# Main.net
KiCad netlist of a schematic drawn in EAGLE
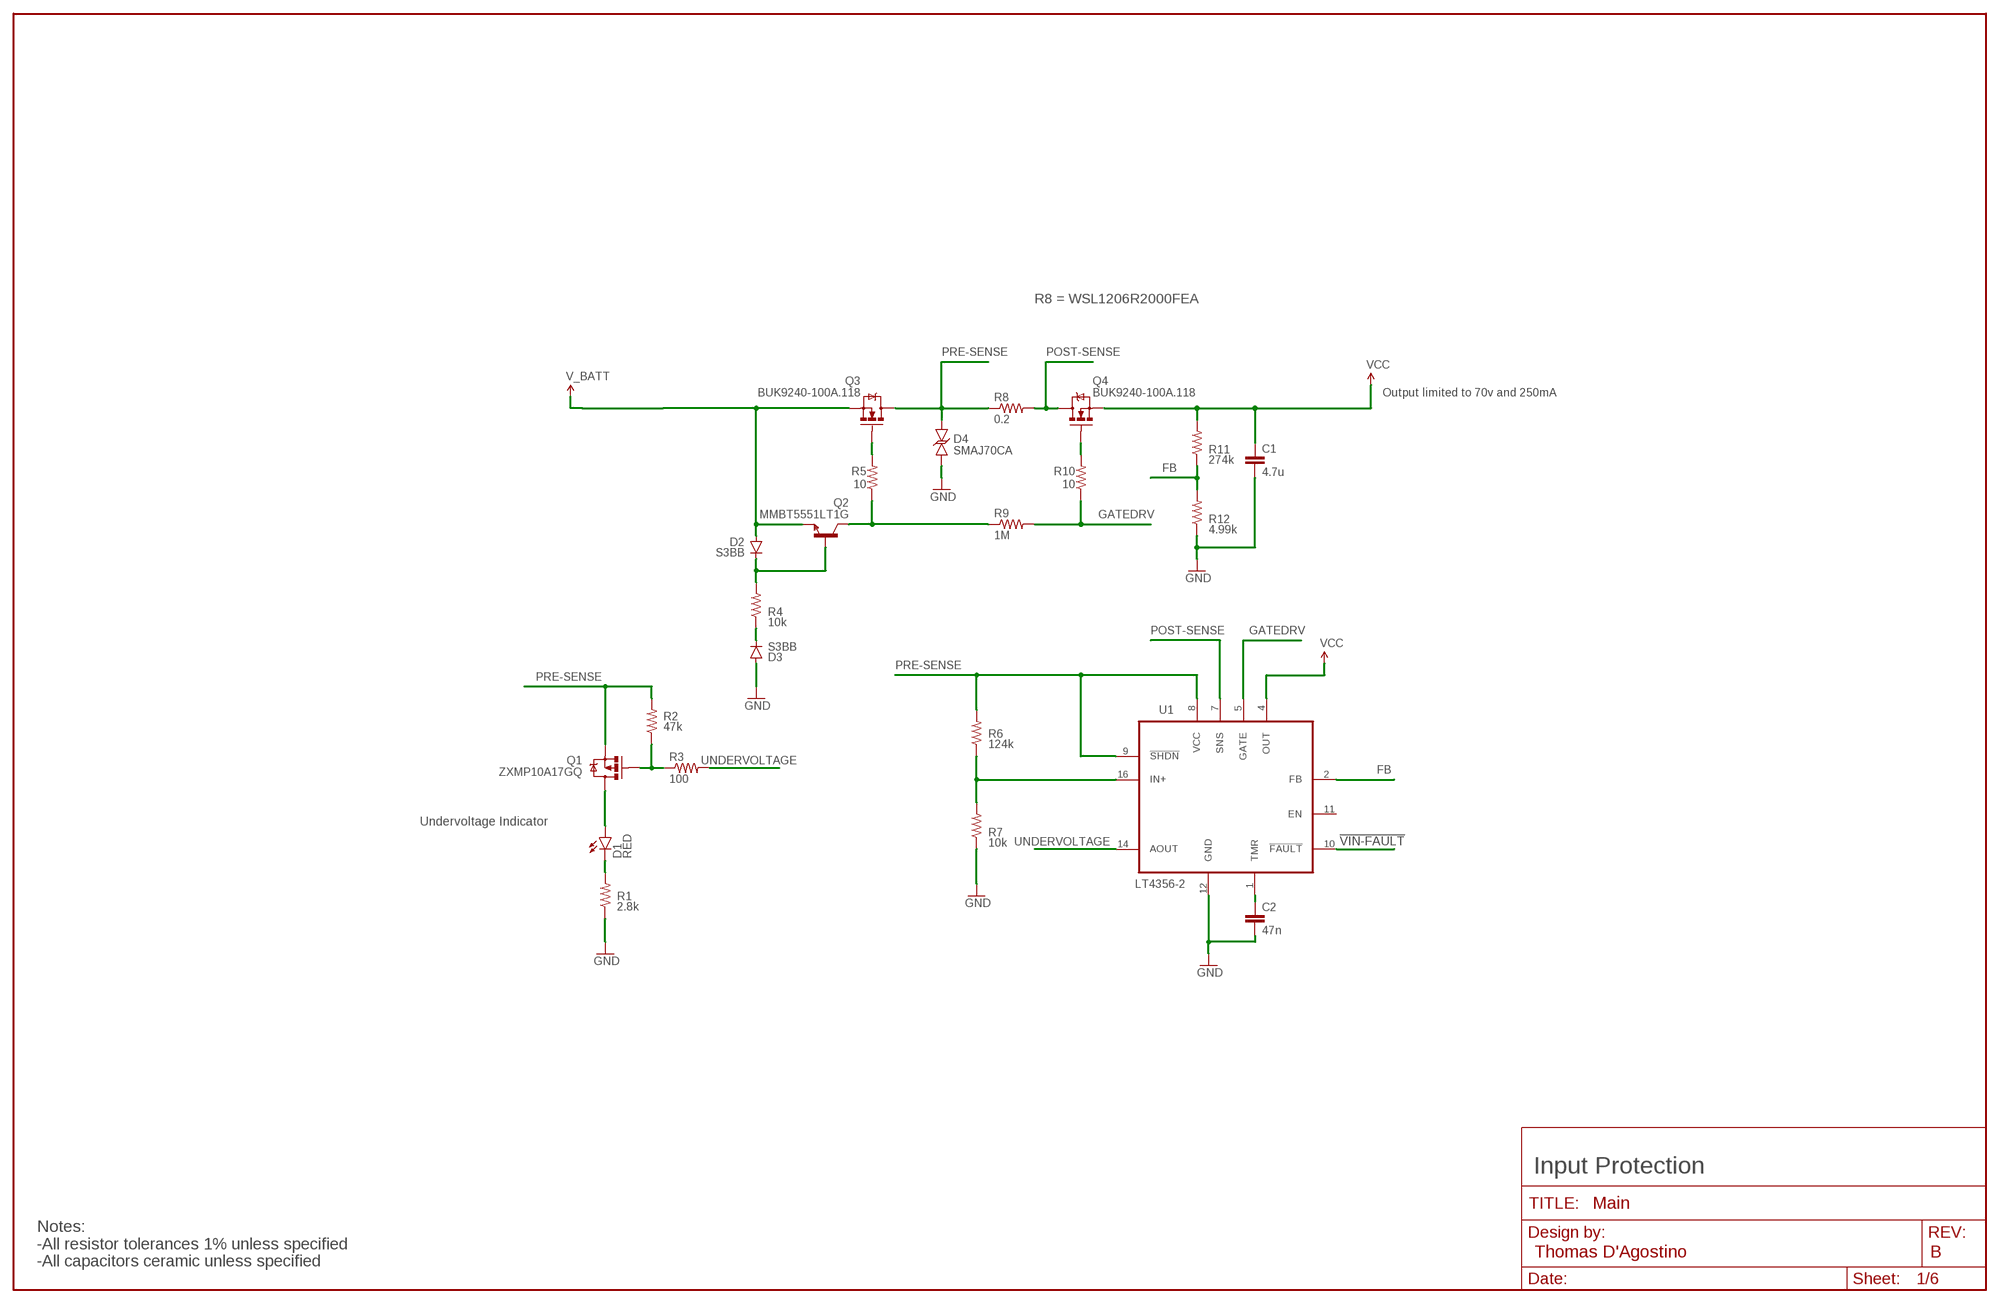
[diagram p0: schematic, sheet 1]
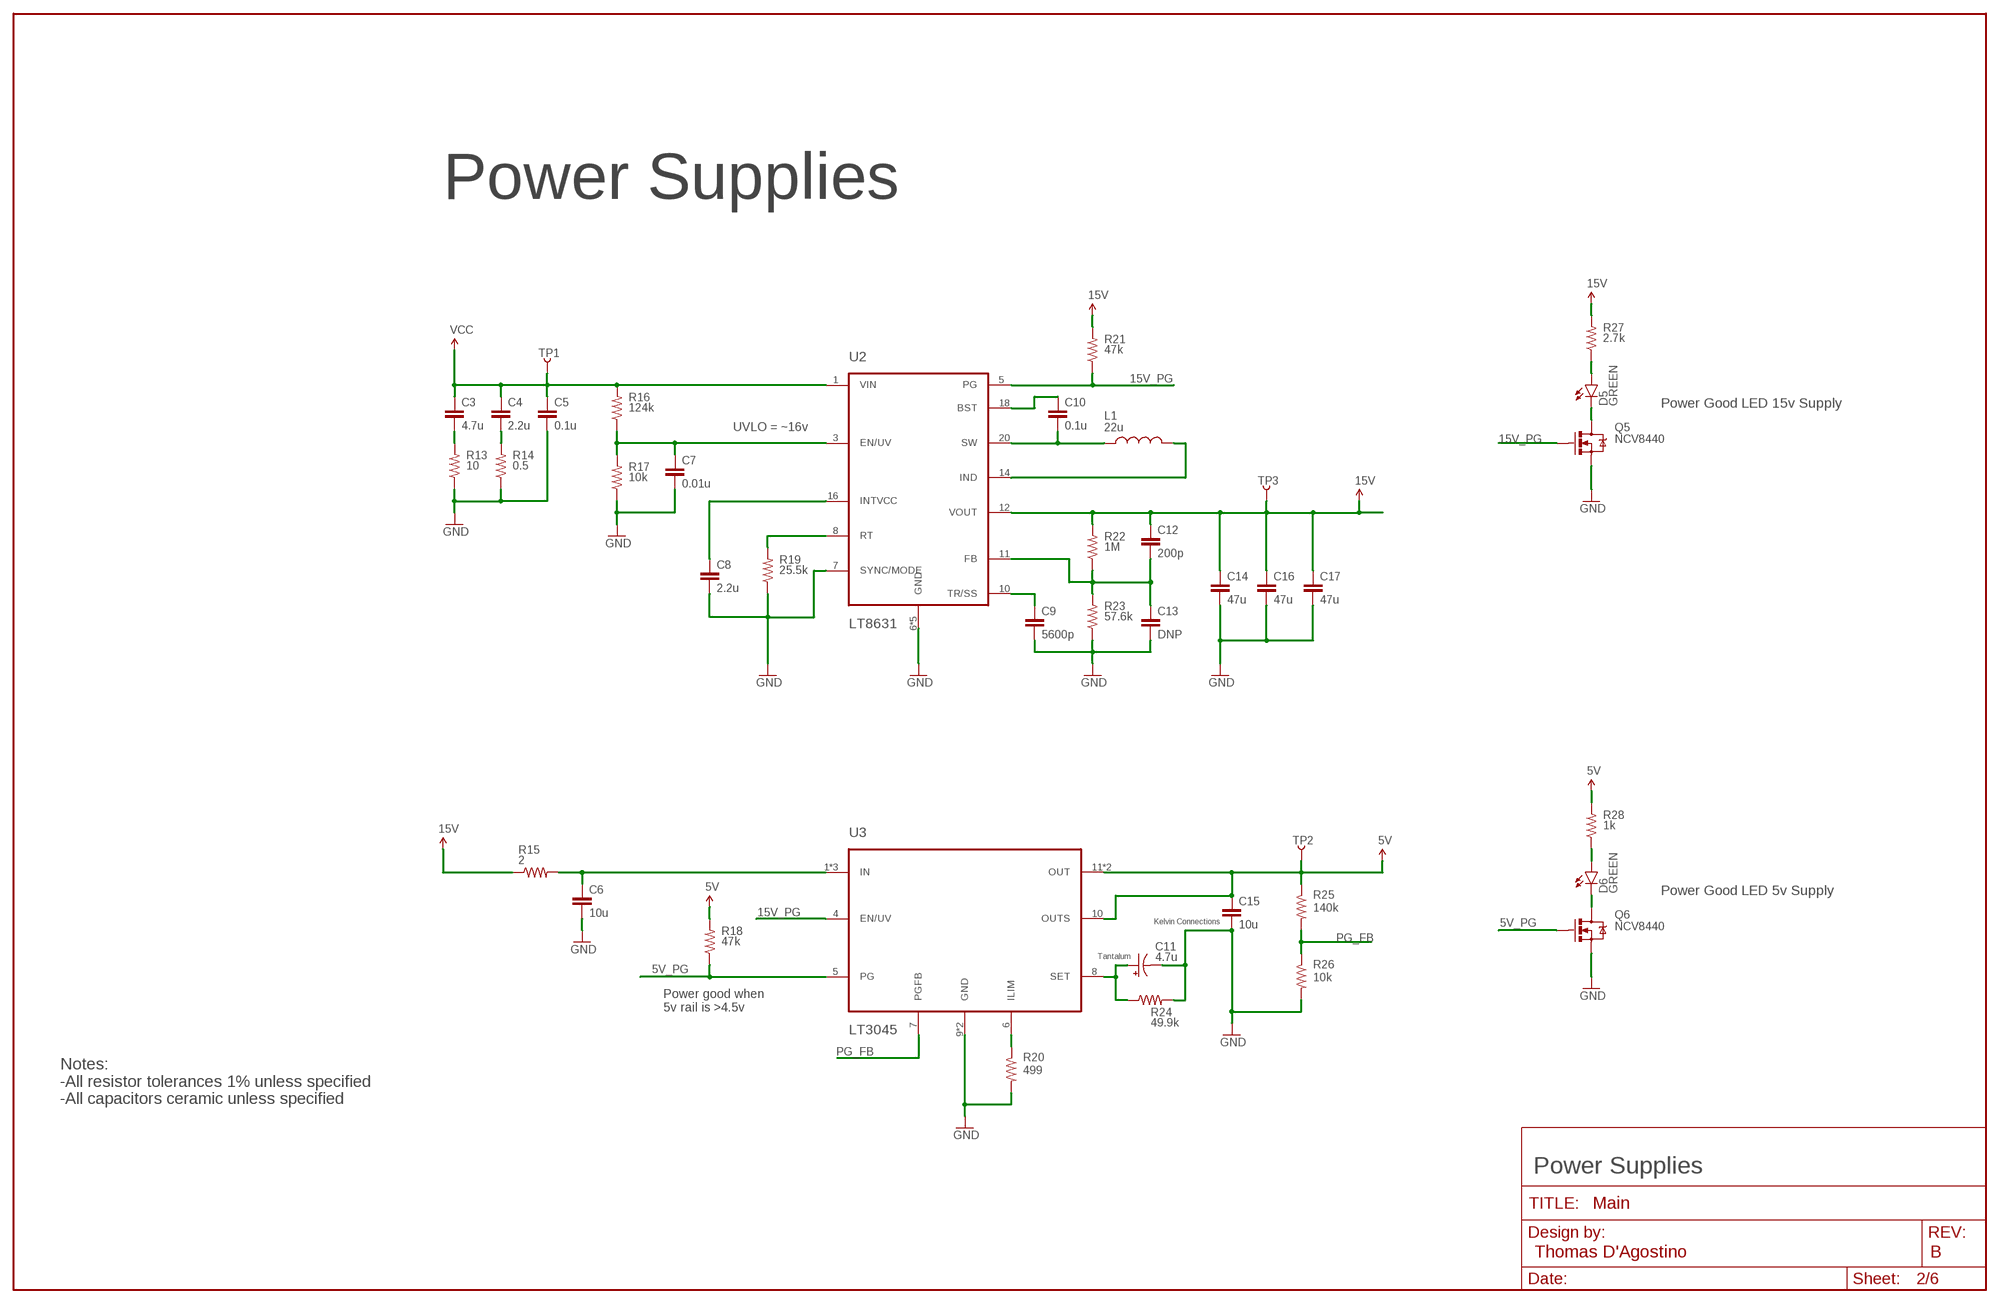
[diagram p1: schematic, sheet 2]
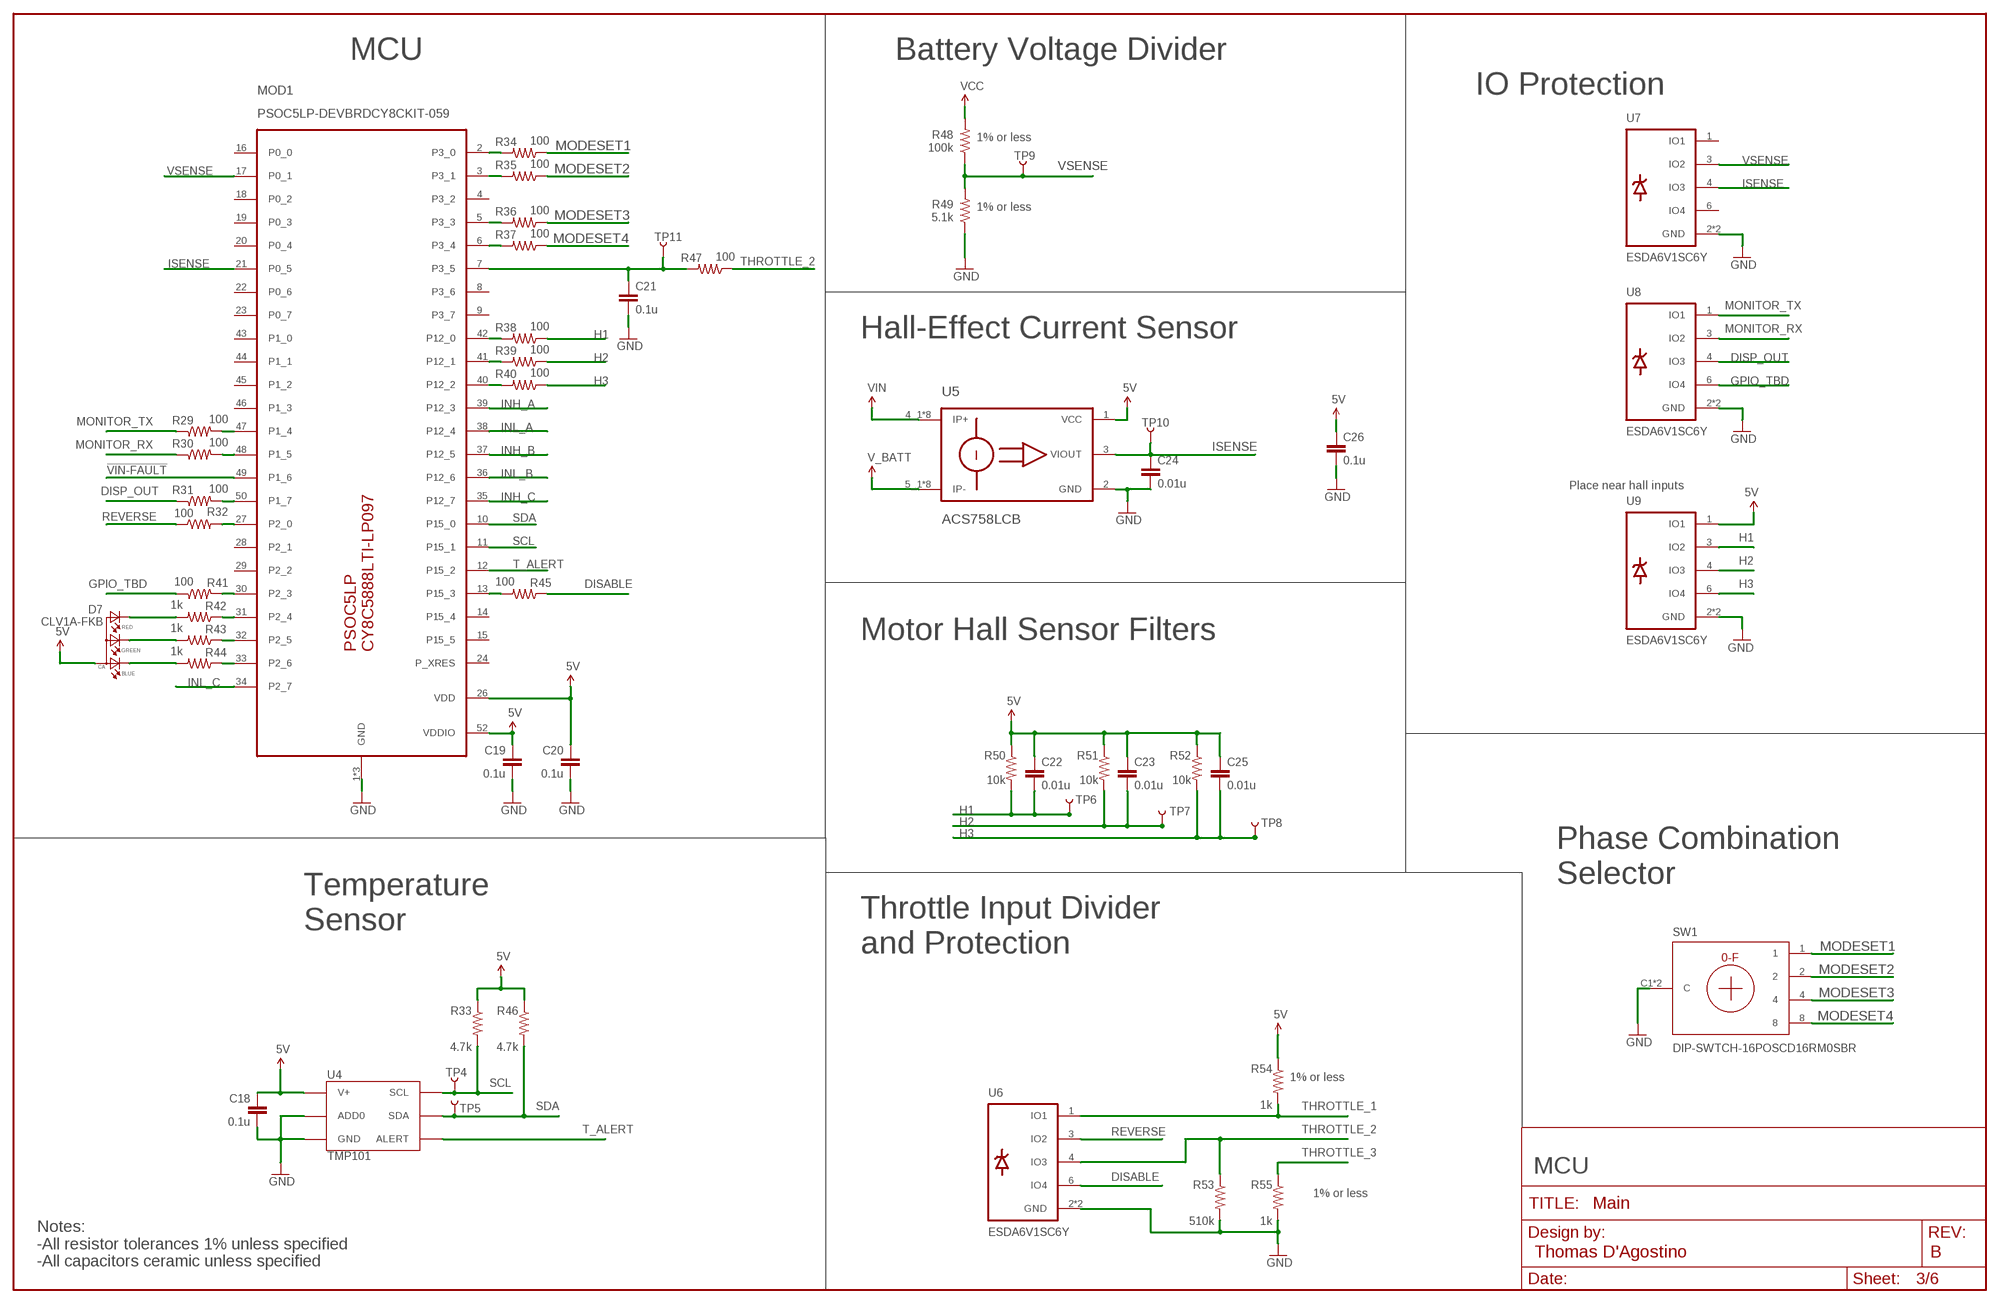
[diagram p2: schematic, sheet 3]
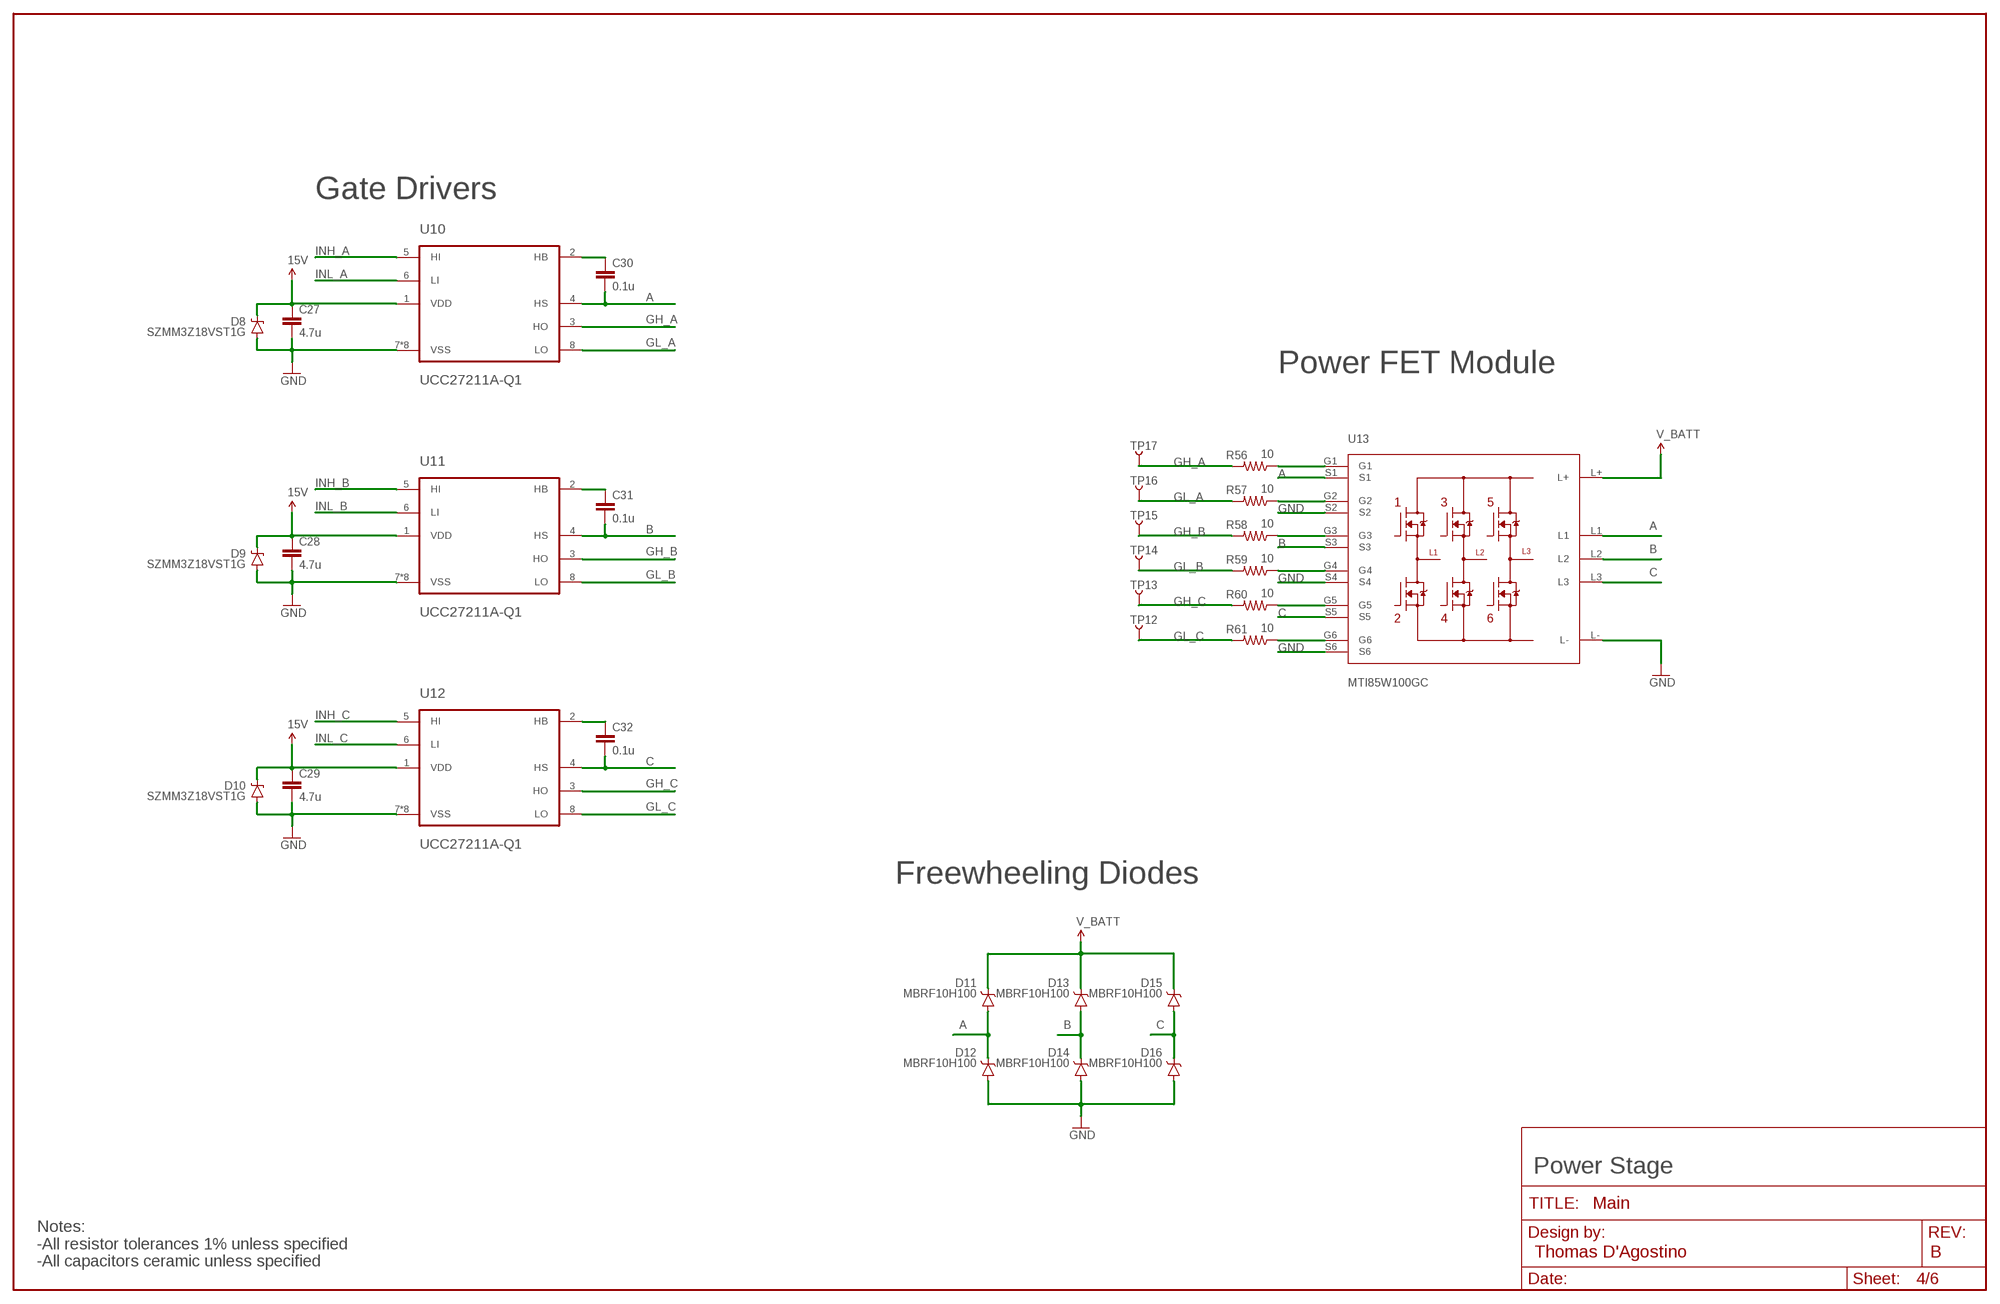
[diagram p3: schematic, sheet 4]
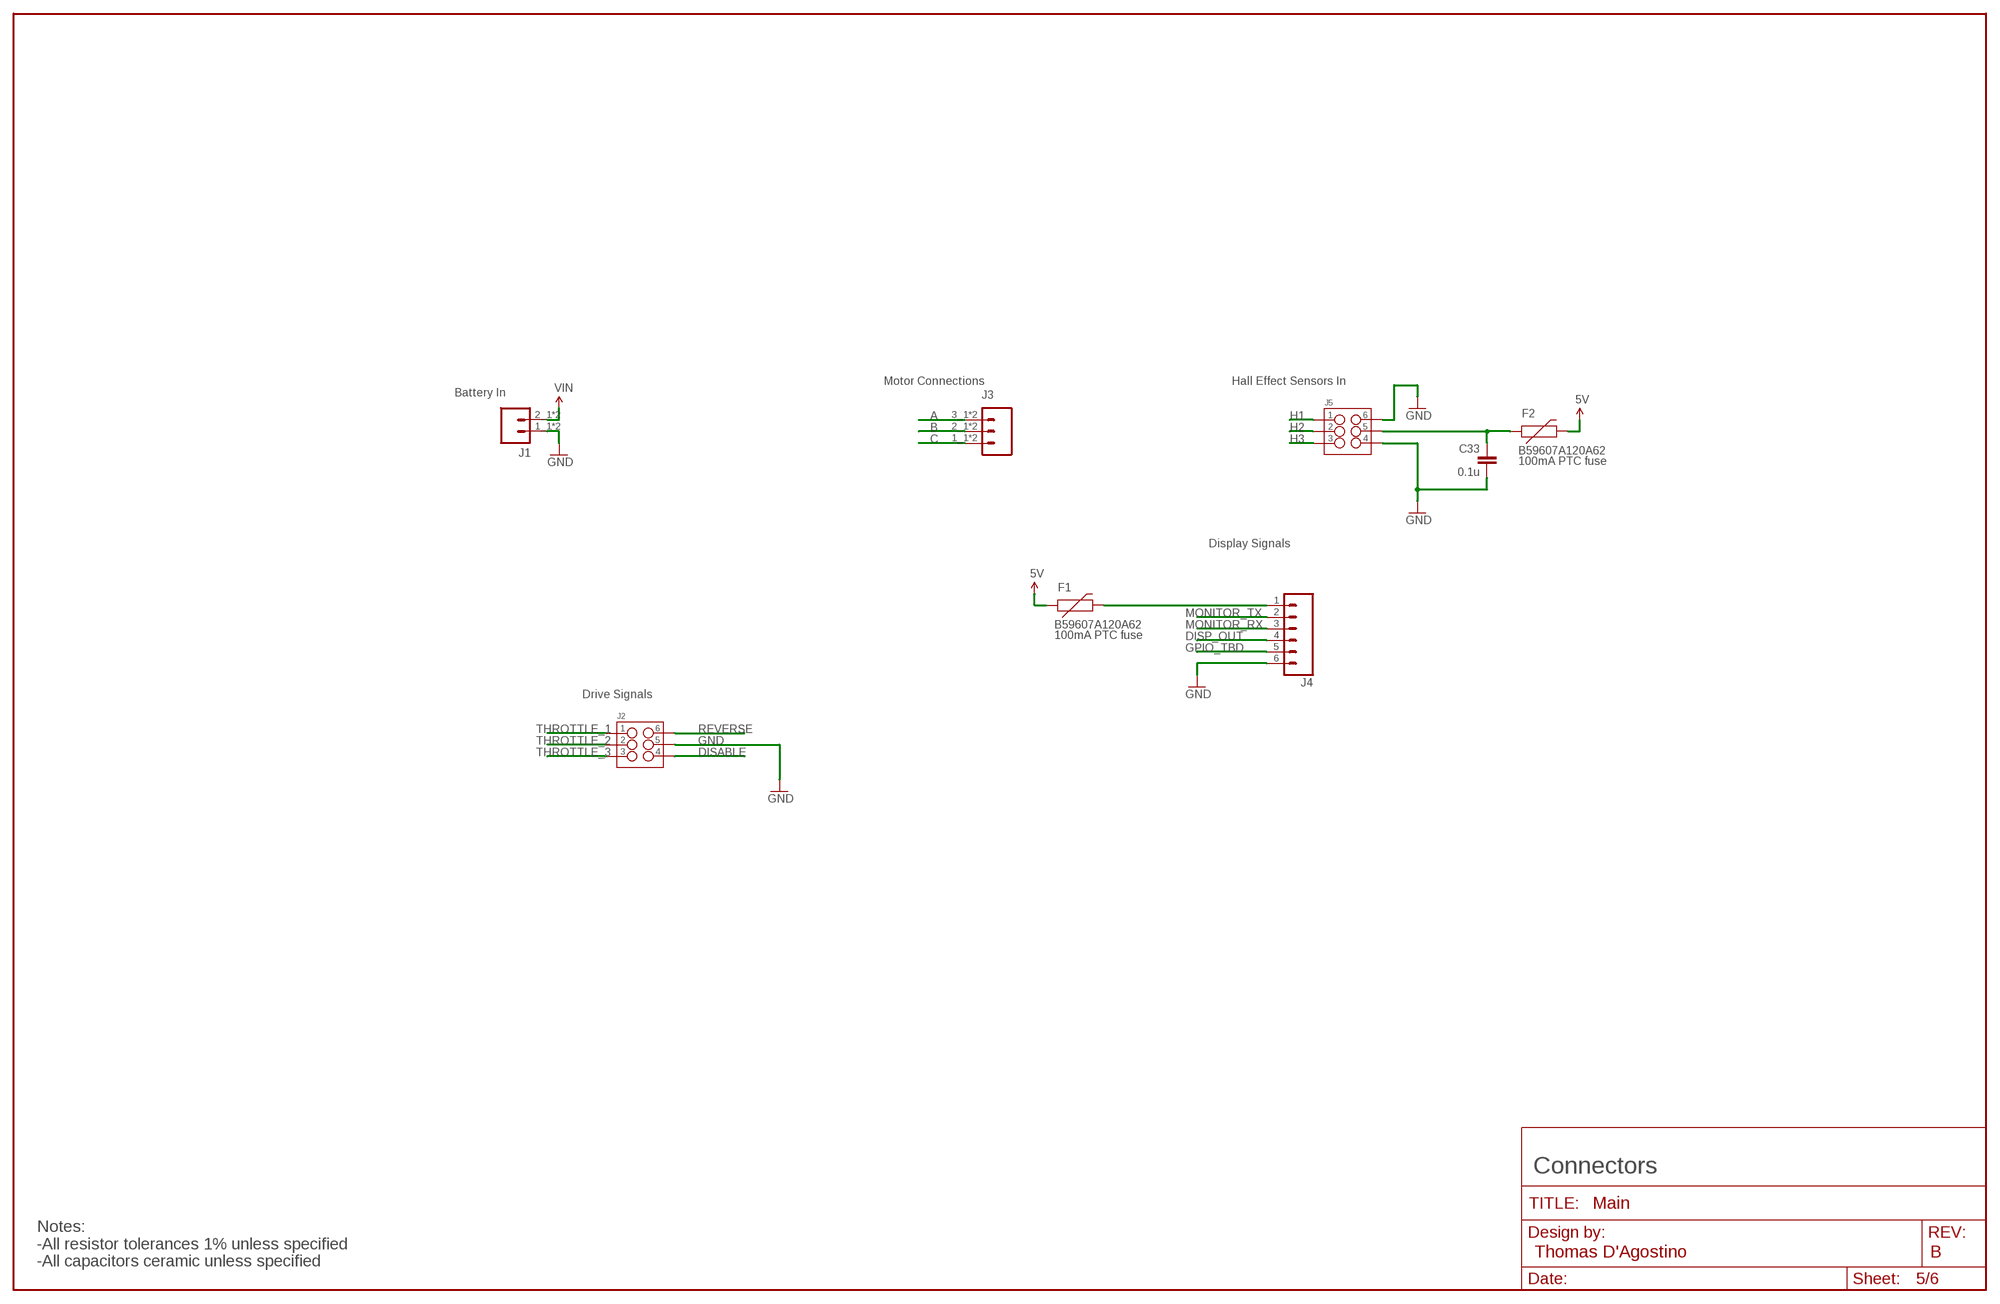
[diagram p4: schematic, sheet 5]
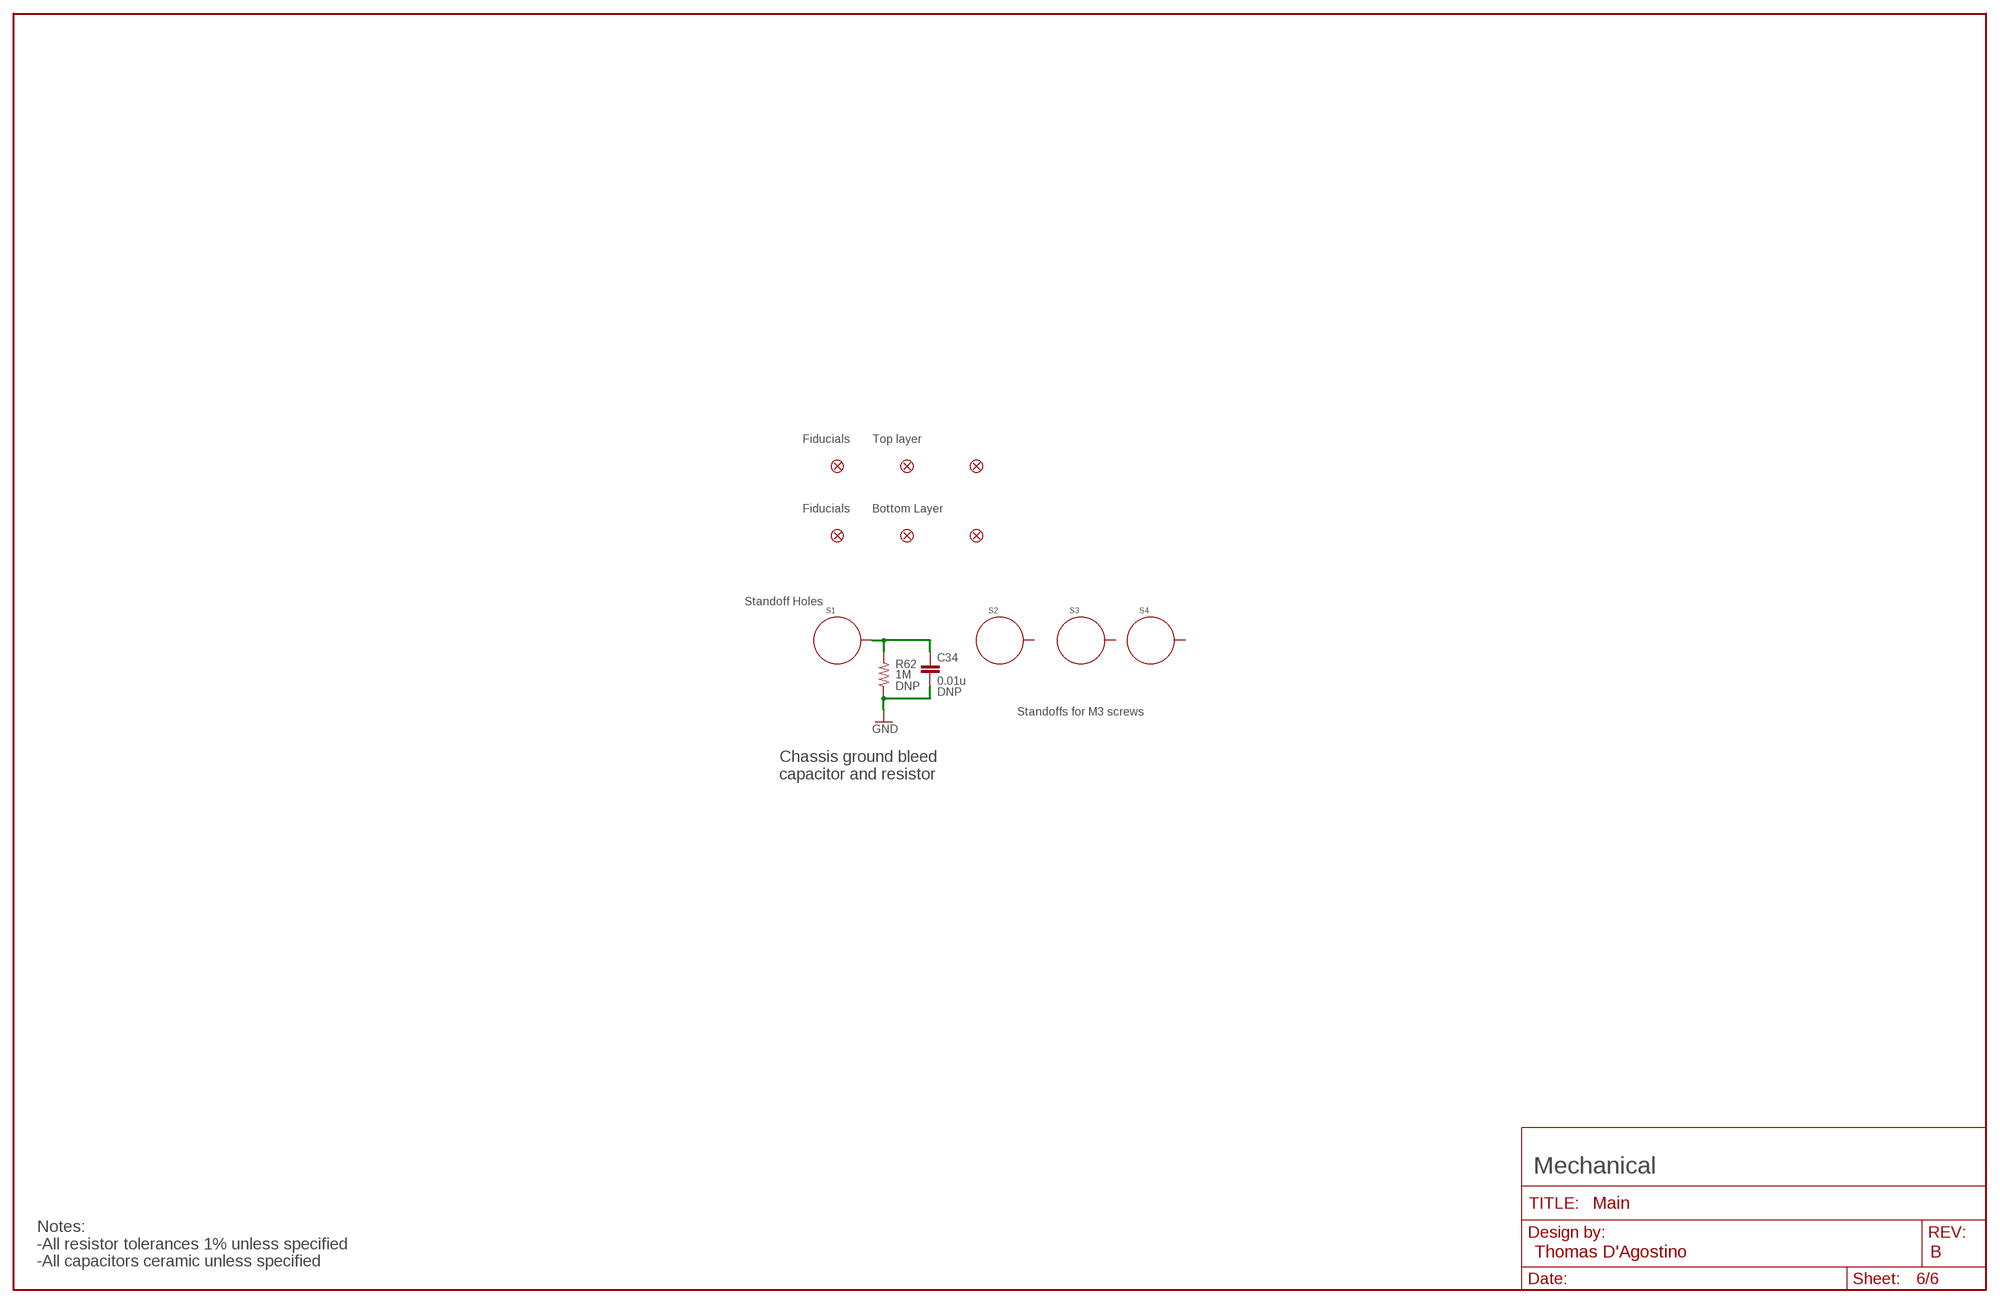
[diagram p5: schematic, sheet 6]

(export (version "E")
  (design (tool "Eeschema 10.0.6"))
  (components
    (comp (ref "C33")
      (value "0.1u")
      (footprint "eagle-import:0805")
      (libsource (lib "eagle-import") (part "CAP0805"))
    )
    (comp (ref "F1")
      (value "B59607A120A62")
      (footprint "eagle-import:1210")
      (libsource (lib "eagle-import") (part "PTC1210"))
    )
    (comp (ref "F2")
      (value "B59607A120A62")
      (footprint "eagle-import:1210")
      (libsource (lib "eagle-import") (part "PTC1210"))
    )
    (comp (ref "FRAME5")
      (value "FRAME-LEDGER")
      (footprint "eagle-import:CREATIVE_COMMONS")
      (libsource (lib "eagle-import") (part "FRAME-LEDGER"))
    )
    (comp (ref "J1")
      (value "M02MINIFIT-SR")
      (footprint "eagle-import:MINIFIT_SR")
      (libsource (lib "eagle-import") (part "M02MINIFIT-SR"))
    )
    (comp (ref "J2")
      (value "M03X2MINIFIT_JR")
      (footprint "eagle-import:2X03_MINIFIT_JR")
      (libsource (lib "eagle-import") (part "M03X2MINIFIT_JR"))
    )
    (comp (ref "J3")
      (value "M03MINIFIT-SR3")
      (footprint "eagle-import:MINIFIT-SRX3")
      (libsource (lib "eagle-import") (part "M03MINIFIT-SR3"))
    )
    (comp (ref "J4")
      (value "M06SILK_FEMALE_PTH")
      (footprint "eagle-import:1X06")
      (libsource (lib "eagle-import") (part "M06SILK_FEMALE_PTH"))
    )
    (comp (ref "J5")
      (value "M03X2MINIFIT_JR")
      (footprint "eagle-import:2X03_MINIFIT_JR")
      (libsource (lib "eagle-import") (part "M03X2MINIFIT_JR"))
    )
    (comp (ref "C18")
      (value "0.1u")
      (footprint "eagle-import:0805")
      (libsource (lib "eagle-import") (part "CAP0805"))
    )
    (comp (ref "C19")
      (value "0.1u")
      (footprint "eagle-import:0805")
      (libsource (lib "eagle-import") (part "CAP0805"))
    )
    (comp (ref "C20")
      (value "0.1u")
      (footprint "eagle-import:0805")
      (libsource (lib "eagle-import") (part "CAP0805"))
    )
    (comp (ref "C21")
      (value "0.1u")
      (footprint "eagle-import:0805")
      (libsource (lib "eagle-import") (part "CAP0805"))
    )
    (comp (ref "C22")
      (value "0.01u")
      (footprint "eagle-import:0805")
      (libsource (lib "eagle-import") (part "CAP0805"))
    )
    (comp (ref "C23")
      (value "0.01u")
      (footprint "eagle-import:0805")
      (libsource (lib "eagle-import") (part "CAP0805"))
    )
    (comp (ref "C24")
      (value "0.01u")
      (footprint "eagle-import:0805")
      (libsource (lib "eagle-import") (part "CAP0805"))
    )
    (comp (ref "C25")
      (value "0.01u")
      (footprint "eagle-import:0805")
      (libsource (lib "eagle-import") (part "CAP0805"))
    )
    (comp (ref "C26")
      (value "0.1u")
      (footprint "eagle-import:0805")
      (libsource (lib "eagle-import") (part "CAP0805"))
    )
    (comp (ref "D7")
      (value "CLV1A-FKB")
      (footprint "eagle-import:P-LCC-4-3")
      (libsource (lib "eagle-import") (part "0.13_RGB_LEDCLV1A-FKB"))
    )
    (comp (ref "FRAME3")
      (value "FRAME-LEDGER")
      (footprint "eagle-import:CREATIVE_COMMONS")
      (libsource (lib "eagle-import") (part "FRAME-LEDGER"))
    )
    (comp (ref "MOD1")
      (value "PSOC5LP-DEVBRDCY8CKIT-059")
      (footprint "eagle-import:CYKIT059")
      (libsource (lib "eagle-import") (part "PSOC5LP-DEVBRDCY8CKIT-059"))
    )
    (comp (ref "R29")
      (value "100")
      (footprint "eagle-import:0805")
      (libsource (lib "eagle-import") (part "SparkFun-Resistors_RESISTOR0805-RES"))
    )
    (comp (ref "R30")
      (value "100")
      (footprint "eagle-import:0805")
      (libsource (lib "eagle-import") (part "SparkFun-Resistors_RESISTOR0805-RES"))
    )
    (comp (ref "R31")
      (value "100")
      (footprint "eagle-import:0805")
      (libsource (lib "eagle-import") (part "SparkFun-Resistors_RESISTOR0805-RES"))
    )
    (comp (ref "R32")
      (value "100")
      (footprint "eagle-import:0805")
      (libsource (lib "eagle-import") (part "SparkFun-Resistors_RESISTOR0805-RES"))
    )
    (comp (ref "R33")
      (value "4.7k")
      (footprint "eagle-import:0805")
      (libsource (lib "eagle-import") (part "SparkFun-Resistors_RESISTOR0805-RES"))
    )
    (comp (ref "R34")
      (value "100")
      (footprint "eagle-import:0805")
      (libsource (lib "eagle-import") (part "SparkFun-Resistors_RESISTOR0805-RES"))
    )
    (comp (ref "R35")
      (value "100")
      (footprint "eagle-import:0805")
      (libsource (lib "eagle-import") (part "SparkFun-Resistors_RESISTOR0805-RES"))
    )
    (comp (ref "R36")
      (value "100")
      (footprint "eagle-import:0805")
      (libsource (lib "eagle-import") (part "SparkFun-Resistors_RESISTOR0805-RES"))
    )
    (comp (ref "R37")
      (value "100")
      (footprint "eagle-import:0805")
      (libsource (lib "eagle-import") (part "SparkFun-Resistors_RESISTOR0805-RES"))
    )
    (comp (ref "R38")
      (value "100")
      (footprint "eagle-import:0805")
      (libsource (lib "eagle-import") (part "SparkFun-Resistors_RESISTOR0805-RES"))
    )
    (comp (ref "R39")
      (value "100")
      (footprint "eagle-import:0805")
      (libsource (lib "eagle-import") (part "SparkFun-Resistors_RESISTOR0805-RES"))
    )
    (comp (ref "R40")
      (value "100")
      (footprint "eagle-import:0805")
      (libsource (lib "eagle-import") (part "SparkFun-Resistors_RESISTOR0805-RES"))
    )
    (comp (ref "R41")
      (value "100")
      (footprint "eagle-import:0805")
      (libsource (lib "eagle-import") (part "SparkFun-Resistors_RESISTOR0805-RES"))
    )
    (comp (ref "R42")
      (value "1k")
      (footprint "eagle-import:0805")
      (libsource (lib "eagle-import") (part "SparkFun-Resistors_RESISTOR0805-RES"))
    )
    (comp (ref "R43")
      (value "1k")
      (footprint "eagle-import:0805")
      (libsource (lib "eagle-import") (part "SparkFun-Resistors_RESISTOR0805-RES"))
    )
    (comp (ref "R44")
      (value "1k")
      (footprint "eagle-import:0805")
      (libsource (lib "eagle-import") (part "SparkFun-Resistors_RESISTOR0805-RES"))
    )
    (comp (ref "R45")
      (value "100")
      (footprint "eagle-import:0805")
      (libsource (lib "eagle-import") (part "SparkFun-Resistors_RESISTOR0805-RES"))
    )
    (comp (ref "R46")
      (value "4.7k")
      (footprint "eagle-import:0805")
      (libsource (lib "eagle-import") (part "SparkFun-Resistors_RESISTOR0805-RES"))
    )
    (comp (ref "R47")
      (value "100")
      (footprint "eagle-import:0805")
      (libsource (lib "eagle-import") (part "SparkFun-Resistors_RESISTOR0805-RES"))
    )
    (comp (ref "R48")
      (value "100k")
      (footprint "eagle-import:1206")
      (libsource (lib "eagle-import") (part "SparkFun-Resistors_RESISTOR1206"))
    )
    (comp (ref "R49")
      (value "5.1k")
      (footprint "eagle-import:1206")
      (libsource (lib "eagle-import") (part "SparkFun-Resistors_RESISTOR1206"))
    )
    (comp (ref "R50")
      (value "10k")
      (footprint "eagle-import:0805")
      (libsource (lib "eagle-import") (part "SparkFun-Resistors_RESISTOR0805-RES"))
    )
    (comp (ref "R51")
      (value "10k")
      (footprint "eagle-import:0805")
      (libsource (lib "eagle-import") (part "SparkFun-Resistors_RESISTOR0805-RES"))
    )
    (comp (ref "R52")
      (value "10k")
      (footprint "eagle-import:0805")
      (libsource (lib "eagle-import") (part "SparkFun-Resistors_RESISTOR0805-RES"))
    )
    (comp (ref "R53")
      (value "510k")
      (footprint "eagle-import:0805")
      (libsource (lib "eagle-import") (part "SparkFun-Resistors_RESISTOR0805-RES"))
    )
    (comp (ref "R54")
      (value "1k")
      (footprint "eagle-import:0805")
      (libsource (lib "eagle-import") (part "SparkFun-Resistors_RESISTOR0805-RES"))
    )
    (comp (ref "R55")
      (value "1k")
      (footprint "eagle-import:0805")
      (libsource (lib "eagle-import") (part "SparkFun-Resistors_RESISTOR0805-RES"))
    )
    (comp (ref "SW1")
      (value "DIP-SWTCH-16POSCD16RM0SBR")
      (footprint "eagle-import:DIP-8MM")
      (libsource (lib "eagle-import") (part "DIP-SWTCH-16POSCD16RM0SBR"))
    )
    (comp (ref "TP4")
      (value "TEST-POINTRCT-0C")
      (footprint "eagle-import:TEST-POINT-MINI")
      (libsource (lib "eagle-import") (part "TEST-POINTRCT-0C"))
    )
    (comp (ref "TP5")
      (value "TEST-POINTRCT-0C")
      (footprint "eagle-import:TEST-POINT-MINI")
      (libsource (lib "eagle-import") (part "TEST-POINTRCT-0C"))
    )
    (comp (ref "TP6")
      (value "TEST-POINTRCT-0C")
      (footprint "eagle-import:TEST-POINT-MINI")
      (libsource (lib "eagle-import") (part "TEST-POINTRCT-0C"))
    )
    (comp (ref "TP7")
      (value "TEST-POINTRCT-0C")
      (footprint "eagle-import:TEST-POINT-MINI")
      (libsource (lib "eagle-import") (part "TEST-POINTRCT-0C"))
    )
    (comp (ref "TP8")
      (value "TEST-POINTRCT-0C")
      (footprint "eagle-import:TEST-POINT-MINI")
      (libsource (lib "eagle-import") (part "TEST-POINTRCT-0C"))
    )
    (comp (ref "TP9")
      (value "TEST-POINTRCT-0C")
      (footprint "eagle-import:TEST-POINT-MINI")
      (libsource (lib "eagle-import") (part "TEST-POINTRCT-0C"))
    )
    (comp (ref "TP10")
      (value "TEST-POINTRCT-0C")
      (footprint "eagle-import:TEST-POINT-MINI")
      (libsource (lib "eagle-import") (part "TEST-POINTRCT-0C"))
    )
    (comp (ref "TP11")
      (value "TEST-POINTRCT-0C")
      (footprint "eagle-import:TEST-POINT-MINI")
      (libsource (lib "eagle-import") (part "TEST-POINTRCT-0C"))
    )
    (comp (ref "U4")
      (value "TMP101")
      (footprint "eagle-import:SOT23-6")
      (libsource (lib "eagle-import") (part "TMP101"))
    )
    (comp (ref "U5")
      (value "ACS758LCB")
      (footprint "eagle-import:CB5PIN")
      (libsource (lib "eagle-import") (part "ACS758LCB"))
    )
    (comp (ref "U6")
      (value "ESDA6V1SC6Y")
      (footprint "eagle-import:SOT23-6")
      (libsource (lib "eagle-import") (part "ESDA6V1SC6Y"))
    )
    (comp (ref "U7")
      (value "ESDA6V1SC6Y")
      (footprint "eagle-import:SOT23-6")
      (libsource (lib "eagle-import") (part "ESDA6V1SC6Y"))
    )
    (comp (ref "U8")
      (value "ESDA6V1SC6Y")
      (footprint "eagle-import:SOT23-6")
      (libsource (lib "eagle-import") (part "ESDA6V1SC6Y"))
    )
    (comp (ref "U9")
      (value "ESDA6V1SC6Y")
      (footprint "eagle-import:SOT23-6")
      (libsource (lib "eagle-import") (part "ESDA6V1SC6Y"))
    )
    (comp (ref "C3")
      (value "4.7u")
      (footprint "eagle-import:1210")
      (libsource (lib "eagle-import") (part "CAP1210"))
    )
    (comp (ref "C4")
      (value "2.2u")
      (footprint "eagle-import:1210")
      (libsource (lib "eagle-import") (part "CAP1210"))
    )
    (comp (ref "C5")
      (value "0.1u")
      (footprint "eagle-import:0805")
      (libsource (lib "eagle-import") (part "CAP0805"))
    )
    (comp (ref "C6")
      (value "10u")
      (footprint "eagle-import:1210")
      (libsource (lib "eagle-import") (part "CAP1210"))
    )
    (comp (ref "C7")
      (value "0.01u")
      (footprint "eagle-import:0805")
      (libsource (lib "eagle-import") (part "CAP0805"))
    )
    (comp (ref "C8")
      (value "2.2u")
      (footprint "eagle-import:0805")
      (libsource (lib "eagle-import") (part "CAP0805"))
    )
    (comp (ref "C9")
      (value "5600p")
      (footprint "eagle-import:0805")
      (libsource (lib "eagle-import") (part "CAP0805"))
    )
    (comp (ref "C10")
      (value "0.1u")
      (footprint "eagle-import:0805")
      (libsource (lib "eagle-import") (part "CAP0805"))
    )
    (comp (ref "C11")
      (value "4.7u")
      (footprint "eagle-import:EIA3216")
      (libsource (lib "eagle-import") (part "CAP_POL1206"))
    )
    (comp (ref "C12")
      (value "200p")
      (footprint "eagle-import:0805")
      (libsource (lib "eagle-import") (part "CAP0805"))
    )
    (comp (ref "C13")
      (value "DNP")
      (footprint "eagle-import:0805")
      (libsource (lib "eagle-import") (part "CAP0805"))
    )
    (comp (ref "C14")
      (value "47u")
      (footprint "eagle-import:1210")
      (libsource (lib "eagle-import") (part "CAP1210"))
    )
    (comp (ref "C15")
      (value "10u")
      (footprint "eagle-import:1210")
      (libsource (lib "eagle-import") (part "CAP1210"))
    )
    (comp (ref "C16")
      (value "47u")
      (footprint "eagle-import:1210")
      (libsource (lib "eagle-import") (part "CAP1210"))
    )
    (comp (ref "C17")
      (value "47u")
      (footprint "eagle-import:1210")
      (libsource (lib "eagle-import") (part "CAP1210"))
    )
    (comp (ref "D5")
      (value "GREEN")
      (footprint "eagle-import:LED-1206")
      (libsource (lib "eagle-import") (part "LED-RED1206"))
    )
    (comp (ref "D6")
      (value "GREEN")
      (footprint "eagle-import:LED-1206")
      (libsource (lib "eagle-import") (part "LED-RED1206"))
    )
    (comp (ref "FRAME2")
      (value "FRAME-LEDGER")
      (footprint "eagle-import:CREATIVE_COMMONS")
      (libsource (lib "eagle-import") (part "FRAME-LEDGER"))
    )
    (comp (ref "L1")
      (value "22u")
      (footprint "eagle-import:IND_SMD_SRP7050TA")
      (libsource (lib "eagle-import") (part "INDUCTORSRP7050TA-220M"))
    )
    (comp (ref "Q5")
      (value "NCV8440")
      (footprint "eagle-import:SOT223")
      (libsource (lib "eagle-import") (part "MOSFET-NCHANNELNCV8440"))
    )
    (comp (ref "Q6")
      (value "NCV8440")
      (footprint "eagle-import:SOT223")
      (libsource (lib "eagle-import") (part "MOSFET-NCHANNELNCV8440"))
    )
    (comp (ref "R13")
      (value "10")
      (footprint "eagle-import:0805")
      (libsource (lib "eagle-import") (part "SparkFun-Resistors_RESISTOR0805-RES"))
    )
    (comp (ref "R14")
      (value "0.5")
      (footprint "eagle-import:0805")
      (libsource (lib "eagle-import") (part "SparkFun-Resistors_RESISTOR0805-RES"))
    )
    (comp (ref "R15")
      (value "2")
      (footprint "eagle-import:1206")
      (libsource (lib "eagle-import") (part "RESISTOR1206"))
    )
    (comp (ref "R16")
      (value "124k")
      (footprint "eagle-import:0805")
      (libsource (lib "eagle-import") (part "SparkFun-Resistors_RESISTOR0805-RES"))
    )
    (comp (ref "R17")
      (value "10k")
      (footprint "eagle-import:0805")
      (libsource (lib "eagle-import") (part "SparkFun-Resistors_RESISTOR0805-RES"))
    )
    (comp (ref "R18")
      (value "47k")
      (footprint "eagle-import:0805")
      (libsource (lib "eagle-import") (part "SparkFun-Resistors_RESISTOR0805-RES"))
    )
    (comp (ref "R19")
      (value "25.5k")
      (footprint "eagle-import:0805")
      (libsource (lib "eagle-import") (part "SparkFun-Resistors_RESISTOR0805-RES"))
    )
    (comp (ref "R20")
      (value "499")
      (footprint "eagle-import:0805")
      (libsource (lib "eagle-import") (part "SparkFun-Resistors_RESISTOR0805-RES"))
    )
    (comp (ref "R21")
      (value "47k")
      (footprint "eagle-import:0805")
      (libsource (lib "eagle-import") (part "SparkFun-Resistors_RESISTOR0805-RES"))
    )
    (comp (ref "R22")
      (value "1M")
      (footprint "eagle-import:0805")
      (libsource (lib "eagle-import") (part "SparkFun-Resistors_RESISTOR0805-RES"))
    )
    (comp (ref "R23")
      (value "57.6k")
      (footprint "eagle-import:0805")
      (libsource (lib "eagle-import") (part "SparkFun-Resistors_RESISTOR0805-RES"))
    )
    (comp (ref "R24")
      (value "49.9k")
      (footprint "eagle-import:0805")
      (libsource (lib "eagle-import") (part "SparkFun-Resistors_RESISTOR0805-RES"))
    )
    (comp (ref "R25")
      (value "140k")
      (footprint "eagle-import:0805")
      (libsource (lib "eagle-import") (part "SparkFun-Resistors_RESISTOR0805-RES"))
    )
    (comp (ref "R26")
      (value "10k")
      (footprint "eagle-import:0805")
      (libsource (lib "eagle-import") (part "SparkFun-Resistors_RESISTOR0805-RES"))
    )
    (comp (ref "R27")
      (value "2.7k")
      (footprint "eagle-import:0805")
      (libsource (lib "eagle-import") (part "SparkFun-Resistors_RESISTOR0805-RES"))
    )
    (comp (ref "R28")
      (value "1k")
      (footprint "eagle-import:0805")
      (libsource (lib "eagle-import") (part "SparkFun-Resistors_RESISTOR0805-RES"))
    )
    (comp (ref "TP1")
      (value "TEST-POINTRCT-0C")
      (footprint "eagle-import:TEST-POINT-MINI")
      (libsource (lib "eagle-import") (part "TEST-POINTRCT-0C"))
    )
    (comp (ref "TP2")
      (value "TEST-POINTRCT-0C")
      (footprint "eagle-import:TEST-POINT-MINI")
      (libsource (lib "eagle-import") (part "TEST-POINTRCT-0C"))
    )
    (comp (ref "TP3")
      (value "TEST-POINTRCT-0C")
      (footprint "eagle-import:TEST-POINT-MINI")
      (libsource (lib "eagle-import") (part "TEST-POINTRCT-0C"))
    )
    (comp (ref "U2")
      (value "LT8631")
      (footprint "eagle-import:TSSOP-20-FE")
      (libsource (lib "eagle-import") (part "LT8631"))
    )
    (comp (ref "U3")
      (value "LT3045")
      (footprint "eagle-import:MSOP-12-EP")
      (libsource (lib "eagle-import") (part "LT3045"))
    )
    (comp (ref "C27")
      (value "4.7u")
      (footprint "eagle-import:1210")
      (libsource (lib "eagle-import") (part "CAP1210"))
    )
    (comp (ref "C28")
      (value "4.7u")
      (footprint "eagle-import:1210")
      (libsource (lib "eagle-import") (part "CAP1210"))
    )
    (comp (ref "C29")
      (value "4.7u")
      (footprint "eagle-import:1210")
      (libsource (lib "eagle-import") (part "CAP1210"))
    )
    (comp (ref "C30")
      (value "0.1u")
      (footprint "eagle-import:0805")
      (libsource (lib "eagle-import") (part "CAP0805"))
    )
    (comp (ref "C31")
      (value "0.1u")
      (footprint "eagle-import:0805")
      (libsource (lib "eagle-import") (part "CAP0805"))
    )
    (comp (ref "C32")
      (value "0.1u")
      (footprint "eagle-import:0805")
      (libsource (lib "eagle-import") (part "CAP0805"))
    )
    (comp (ref "D8")
      (value "SZMM3Z18VST1G")
      (footprint "eagle-import:SOD-323")
      (libsource (lib "eagle-import") (part "DIODE-ZENERSZMM3Z18VST1G"))
    )
    (comp (ref "D9")
      (value "SZMM3Z18VST1G")
      (footprint "eagle-import:SOD-323")
      (libsource (lib "eagle-import") (part "DIODE-ZENERSZMM3Z18VST1G"))
    )
    (comp (ref "D10")
      (value "SZMM3Z18VST1G")
      (footprint "eagle-import:SOD-323")
      (libsource (lib "eagle-import") (part "DIODE-ZENERSZMM3Z18VST1G"))
    )
    (comp (ref "D11")
      (value "MBRF10H100")
      (footprint "eagle-import:TO220V_2")
      (libsource (lib "eagle-import") (part "DIODE-SCHOTTKY-MBRF1090_V"))
    )
    (comp (ref "D12")
      (value "MBRF10H100")
      (footprint "eagle-import:TO220V_2")
      (libsource (lib "eagle-import") (part "DIODE-SCHOTTKY-MBRF1090_V"))
    )
    (comp (ref "D13")
      (value "MBRF10H100")
      (footprint "eagle-import:TO220V_2")
      (libsource (lib "eagle-import") (part "DIODE-SCHOTTKY-MBRF1090_V"))
    )
    (comp (ref "D14")
      (value "MBRF10H100")
      (footprint "eagle-import:TO220V_2")
      (libsource (lib "eagle-import") (part "DIODE-SCHOTTKY-MBRF1090_V"))
    )
    (comp (ref "D15")
      (value "MBRF10H100")
      (footprint "eagle-import:TO220V_2")
      (libsource (lib "eagle-import") (part "DIODE-SCHOTTKY-MBRF1090_V"))
    )
    (comp (ref "D16")
      (value "MBRF10H100")
      (footprint "eagle-import:TO220V_2")
      (libsource (lib "eagle-import") (part "DIODE-SCHOTTKY-MBRF1090_V"))
    )
    (comp (ref "FRAME4")
      (value "FRAME-LEDGER")
      (footprint "eagle-import:CREATIVE_COMMONS")
      (libsource (lib "eagle-import") (part "FRAME-LEDGER"))
    )
    (comp (ref "R56")
      (value "10")
      (footprint "eagle-import:0805")
      (libsource (lib "eagle-import") (part "SparkFun-Resistors_RESISTOR0805-RES"))
    )
    (comp (ref "R57")
      (value "10")
      (footprint "eagle-import:0805")
      (libsource (lib "eagle-import") (part "SparkFun-Resistors_RESISTOR0805-RES"))
    )
    (comp (ref "R58")
      (value "10")
      (footprint "eagle-import:0805")
      (libsource (lib "eagle-import") (part "SparkFun-Resistors_RESISTOR0805-RES"))
    )
    (comp (ref "R59")
      (value "10")
      (footprint "eagle-import:0805")
      (libsource (lib "eagle-import") (part "SparkFun-Resistors_RESISTOR0805-RES"))
    )
    (comp (ref "R60")
      (value "10")
      (footprint "eagle-import:0805")
      (libsource (lib "eagle-import") (part "SparkFun-Resistors_RESISTOR0805-RES"))
    )
    (comp (ref "R61")
      (value "10")
      (footprint "eagle-import:0805")
      (libsource (lib "eagle-import") (part "SparkFun-Resistors_RESISTOR0805-RES"))
    )
    (comp (ref "TP12")
      (value "TEST-POINTRCT-0C")
      (footprint "eagle-import:TEST-POINT-MINI")
      (libsource (lib "eagle-import") (part "TEST-POINTRCT-0C"))
    )
    (comp (ref "TP13")
      (value "TEST-POINTRCT-0C")
      (footprint "eagle-import:TEST-POINT-MINI")
      (libsource (lib "eagle-import") (part "TEST-POINTRCT-0C"))
    )
    (comp (ref "TP14")
      (value "TEST-POINTRCT-0C")
      (footprint "eagle-import:TEST-POINT-MINI")
      (libsource (lib "eagle-import") (part "TEST-POINTRCT-0C"))
    )
    (comp (ref "TP15")
      (value "TEST-POINTRCT-0C")
      (footprint "eagle-import:TEST-POINT-MINI")
      (libsource (lib "eagle-import") (part "TEST-POINTRCT-0C"))
    )
    (comp (ref "TP16")
      (value "TEST-POINTRCT-0C")
      (footprint "eagle-import:TEST-POINT-MINI")
      (libsource (lib "eagle-import") (part "TEST-POINTRCT-0C"))
    )
    (comp (ref "TP17")
      (value "TEST-POINTRCT-0C")
      (footprint "eagle-import:TEST-POINT-MINI")
      (libsource (lib "eagle-import") (part "TEST-POINTRCT-0C"))
    )
    (comp (ref "U10")
      (value "UCC27211A-Q1")
      (footprint "eagle-import:SOIC-8-EP")
      (libsource (lib "eagle-import") (part "UCC27211A-Q1"))
    )
    (comp (ref "U11")
      (value "UCC27211A-Q1")
      (footprint "eagle-import:SOIC-8-EP")
      (libsource (lib "eagle-import") (part "UCC27211A-Q1"))
    )
    (comp (ref "U12")
      (value "UCC27211A-Q1")
      (footprint "eagle-import:SOIC-8-EP")
      (libsource (lib "eagle-import") (part "UCC27211A-Q1"))
    )
    (comp (ref "U13")
      (value "MTI85W100GC")
      (footprint "eagle-import:ISOPLUS-DIL")
      (libsource (lib "eagle-import") (part "MTI85W100GC"))
    )
    (comp (ref "C34")
      (value "0.01u")
      (footprint "eagle-import:0805")
      (libsource (lib "eagle-import") (part "CAP0805"))
    )
    (comp (ref "FD1")
      (value "FIDUCIAL1X2")
      (footprint "eagle-import:FIDUCIAL-1X2")
      (libsource (lib "eagle-import") (part "FIDUCIAL1X2"))
    )
    (comp (ref "FD2")
      (value "FIDUCIAL1X2")
      (footprint "eagle-import:FIDUCIAL-1X2")
      (libsource (lib "eagle-import") (part "FIDUCIAL1X2"))
    )
    (comp (ref "FD3")
      (value "FIDUCIAL1X2")
      (footprint "eagle-import:FIDUCIAL-1X2")
      (libsource (lib "eagle-import") (part "FIDUCIAL1X2"))
    )
    (comp (ref "FD4")
      (value "FIDUCIAL1X2")
      (footprint "eagle-import:FIDUCIAL-1X2")
      (libsource (lib "eagle-import") (part "FIDUCIAL1X2"))
    )
    (comp (ref "FD5")
      (value "FIDUCIAL1X2")
      (footprint "eagle-import:FIDUCIAL-1X2")
      (libsource (lib "eagle-import") (part "FIDUCIAL1X2"))
    )
    (comp (ref "FD6")
      (value "FIDUCIAL1X2")
      (footprint "eagle-import:FIDUCIAL-1X2")
      (libsource (lib "eagle-import") (part "FIDUCIAL1X2"))
    )
    (comp (ref "FRAME6")
      (value "FRAME-LEDGER")
      (footprint "eagle-import:CREATIVE_COMMONS")
      (libsource (lib "eagle-import") (part "FRAME-LEDGER"))
    )
    (comp (ref "R62")
      (value "1M")
      (footprint "eagle-import:1206")
      (libsource (lib "eagle-import") (part "SparkFun-Resistors_RESISTOR1206"))
    )
    (comp (ref "S1")
      (value "STANDOFF_ELECTRICAL")
      (footprint "eagle-import:STANDOFF-ELECTRICAL")
      (libsource (lib "eagle-import") (part "STANDOFF_ELECTRICAL"))
    )
    (comp (ref "S2")
      (value "STANDOFF_ELECTRICAL")
      (footprint "eagle-import:STANDOFF-ELECTRICAL")
      (libsource (lib "eagle-import") (part "STANDOFF_ELECTRICAL"))
    )
    (comp (ref "S3")
      (value "STANDOFF_ELECTRICAL")
      (footprint "eagle-import:STANDOFF-ELECTRICAL")
      (libsource (lib "eagle-import") (part "STANDOFF_ELECTRICAL"))
    )
    (comp (ref "S4")
      (value "STANDOFF_ELECTRICAL")
      (footprint "eagle-import:STANDOFF-ELECTRICAL")
      (libsource (lib "eagle-import") (part "STANDOFF_ELECTRICAL"))
    )
    (comp (ref "C1")
      (value "4.7u")
      (footprint "eagle-import:1210")
      (libsource (lib "eagle-import") (part "SparkFun-Passives_CAP1210"))
    )
    (comp (ref "C2")
      (value "47n")
      (footprint "eagle-import:0805")
      (libsource (lib "eagle-import") (part "CAP0805"))
    )
    (comp (ref "D1")
      (value "RED")
      (footprint "eagle-import:LED-1206")
      (libsource (lib "eagle-import") (part "LED-RED1206"))
    )
    (comp (ref "D2")
      (value "S3BB")
      (footprint "eagle-import:SMB-DIODE")
      (libsource (lib "eagle-import") (part "DIODES3BB"))
    )
    (comp (ref "D3")
      (value "S3BB")
      (footprint "eagle-import:SMB-DIODE")
      (libsource (lib "eagle-import") (part "DIODES3BB"))
    )
    (comp (ref "D4")
      (value "SMAJ70CA")
      (footprint "eagle-import:SMA-DIODE-BI")
      (libsource (lib "eagle-import") (part "SMAJ70CABIDIRECTIONAL"))
    )
    (comp (ref "FRAME1")
      (value "FRAME-LEDGER")
      (footprint "eagle-import:CREATIVE_COMMONS")
      (libsource (lib "eagle-import") (part "FRAME-LEDGER"))
    )
    (comp (ref "Q1")
      (value "ZXMP10A17GQ")
      (footprint "eagle-import:SOT223")
      (libsource (lib "eagle-import") (part "MOSFET-PCHANNELZXMP10A17GQ"))
    )
    (comp (ref "Q2")
      (value "MMBT5551LT1G")
      (footprint "eagle-import:SOT23-3")
      (libsource (lib "eagle-import") (part "TRANSISTOR_NPNMMBT5551LT1G"))
    )
    (comp (ref "Q3")
      (value "BUK9240-100A.118")
      (footprint "eagle-import:DPAK")
      (libsource (lib "eagle-import") (part "MOSFET-NCHANNELBUK9240-100A.118"))
    )
    (comp (ref "Q4")
      (value "BUK9240-100A.118")
      (footprint "eagle-import:DPAK")
      (libsource (lib "eagle-import") (part "MOSFET-NCHANNELBUK9240-100A.118"))
    )
    (comp (ref "R1")
      (value "2.8k")
      (footprint "eagle-import:1206")
      (libsource (lib "eagle-import") (part "SparkFun-Resistors_RESISTOR1206"))
    )
    (comp (ref "R2")
      (value "47k")
      (footprint "eagle-import:0805")
      (libsource (lib "eagle-import") (part "SparkFun-Resistors_RESISTOR0805-RES"))
    )
    (comp (ref "R3")
      (value "100")
      (footprint "eagle-import:0805")
      (libsource (lib "eagle-import") (part "SparkFun-Resistors_RESISTOR0805-RES"))
    )
    (comp (ref "R4")
      (value "10k")
      (footprint "eagle-import:0805")
      (libsource (lib "eagle-import") (part "SparkFun-Resistors_RESISTOR0805-RES"))
    )
    (comp (ref "R5")
      (value "10")
      (footprint "eagle-import:0805")
      (libsource (lib "eagle-import") (part "SparkFun-Resistors_RESISTOR0805-RES"))
    )
    (comp (ref "R6")
      (value "124k")
      (footprint "eagle-import:0805")
      (libsource (lib "eagle-import") (part "SparkFun-Resistors_RESISTOR0805-RES"))
    )
    (comp (ref "R7")
      (value "10k")
      (footprint "eagle-import:0805")
      (libsource (lib "eagle-import") (part "SparkFun-Resistors_RESISTOR0805-RES"))
    )
    (comp (ref "R8")
      (value "0.2")
      (footprint "eagle-import:1206")
      (libsource (lib "eagle-import") (part "SparkFun-Resistors_RESISTOR1206"))
    )
    (comp (ref "R9")
      (value "1M")
      (footprint "eagle-import:0805")
      (libsource (lib "eagle-import") (part "SparkFun-Resistors_RESISTOR0805-RES"))
    )
    (comp (ref "R10")
      (value "10")
      (footprint "eagle-import:0805")
      (libsource (lib "eagle-import") (part "SparkFun-Resistors_RESISTOR0805-RES"))
    )
    (comp (ref "R11")
      (value "274k")
      (footprint "eagle-import:0805")
      (libsource (lib "eagle-import") (part "SparkFun-Resistors_RESISTOR0805-RES"))
    )
    (comp (ref "R12")
      (value "4.99k")
      (footprint "eagle-import:0805")
      (libsource (lib "eagle-import") (part "SparkFun-Resistors_RESISTOR0805-RES"))
    )
    (comp (ref "U1")
      (value "LT4356-2")
      (footprint "eagle-import:SOIC-16")
      (libsource (lib "eagle-import") (part "LT4356-2"))
    )
  )
  (nets
    (net (code "1") (name "5V") (class "Default")
      (node (ref "C15") (pin "1") (pinfunction "1_1") (pintype "passive"))
      (node (ref "C18") (pin "1") (pinfunction "1_1") (pintype "passive"))
      (node (ref "C19") (pin "1") (pinfunction "1_1") (pintype "passive"))
      (node (ref "C20") (pin "1") (pinfunction "1_1") (pintype "passive"))
      (node (ref "C22") (pin "1") (pinfunction "1_1") (pintype "passive"))
      (node (ref "C23") (pin "1") (pinfunction "1_1") (pintype "passive"))
      (node (ref "C25") (pin "1") (pinfunction "1_1") (pintype "passive"))
      (node (ref "C26") (pin "1") (pinfunction "1_1") (pintype "passive"))
      (node (ref "D7") (pin "2") (pinfunction "ANODE_2") (pintype "passive"))
      (node (ref "F1") (pin "1") (pinfunction "1_1") (pintype "bidirectional"))
      (node (ref "F2") (pin "2") (pinfunction "2_2") (pintype "bidirectional"))
      (node (ref "MOD1") (pin "26") (pinfunction "VDD_26") (pintype "power_in"))
      (node (ref "MOD1") (pin "52") (pinfunction "VDDIO_52") (pintype "power_in"))
      (node (ref "R18") (pin "2") (pinfunction "2_2") (pintype "passive"))
      (node (ref "R25") (pin "1") (pinfunction "1_1") (pintype "passive"))
      (node (ref "R28") (pin "2") (pinfunction "2_2") (pintype "passive"))
      (node (ref "R33") (pin "1") (pinfunction "1_1") (pintype "passive"))
      (node (ref "R46") (pin "1") (pinfunction "1_1") (pintype "passive"))
      (node (ref "R50") (pin "1") (pinfunction "1_1") (pintype "passive"))
      (node (ref "R51") (pin "1") (pinfunction "1_1") (pintype "passive"))
      (node (ref "R52") (pin "1") (pinfunction "1_1") (pintype "passive"))
      (node (ref "R54") (pin "1") (pinfunction "1_1") (pintype "passive"))
      (node (ref "TP2") (pin "P$1") (pinfunction "1_P$1") (pintype "bidirectional"))
      (node (ref "U3") (pin "10") (pinfunction "OUTS_10") (pintype "input"))
      (node (ref "U3") (pin "11") (pinfunction "OUT_11") (pintype "power_in"))
      (node (ref "U3") (pin "12") (pinfunction "OUT_12") (pintype "power_in"))
      (node (ref "U4") (pin "4") (pinfunction "V+_4") (pintype "power_in"))
      (node (ref "U5") (pin "1") (pinfunction "VCC_1") (pintype "power_in"))
      (node (ref "U9") (pin "1") (pinfunction "IO1_1") (pintype "passive"))
    )
    (net (code "2") (name "5V_PG") (class "Default")
      (node (ref "Q6") (pin "1") (pinfunction "G_1") (pintype "passive"))
      (node (ref "R18") (pin "1") (pinfunction "1_1") (pintype "passive"))
      (node (ref "U3") (pin "5") (pinfunction "PG_5") (pintype "open_collector"))
    )
    (net (code "3") (name "15V") (class "Default")
      (node (ref "C12") (pin "1") (pinfunction "1_1") (pintype "passive"))
      (node (ref "C14") (pin "1") (pinfunction "1_1") (pintype "passive"))
      (node (ref "C16") (pin "1") (pinfunction "1_1") (pintype "passive"))
      (node (ref "C17") (pin "1") (pinfunction "1_1") (pintype "passive"))
      (node (ref "C27") (pin "1") (pinfunction "1_1") (pintype "passive"))
      (node (ref "C28") (pin "1") (pinfunction "1_1") (pintype "passive"))
      (node (ref "C29") (pin "1") (pinfunction "1_1") (pintype "passive"))
      (node (ref "D10") (pin "C") (pinfunction "C_C") (pintype "passive"))
      (node (ref "D8") (pin "C") (pinfunction "C_C") (pintype "passive"))
      (node (ref "D9") (pin "C") (pinfunction "C_C") (pintype "passive"))
      (node (ref "R15") (pin "1") (pinfunction "1_1") (pintype "passive"))
      (node (ref "R21") (pin "2") (pinfunction "2_2") (pintype "passive"))
      (node (ref "R22") (pin "2") (pinfunction "2_2") (pintype "passive"))
      (node (ref "R27") (pin "2") (pinfunction "2_2") (pintype "passive"))
      (node (ref "TP3") (pin "P$1") (pinfunction "1_P$1") (pintype "bidirectional"))
      (node (ref "U10") (pin "1") (pinfunction "VDD_1") (pintype "power_in"))
      (node (ref "U11") (pin "1") (pinfunction "VDD_1") (pintype "power_in"))
      (node (ref "U12") (pin "1") (pinfunction "VDD_1") (pintype "power_in"))
      (node (ref "U2") (pin "12") (pinfunction "VOUT_12") (pintype "passive"))
    )
    (net (code "4") (name "15V_PG") (class "Default")
      (node (ref "Q5") (pin "1") (pinfunction "G_1") (pintype "passive"))
      (node (ref "R21") (pin "1") (pinfunction "1_1") (pintype "passive"))
      (node (ref "U2") (pin "5") (pinfunction "PG_5") (pintype "open_collector"))
      (node (ref "U3") (pin "4") (pinfunction "EN/UV_4") (pintype "input"))
    )
    (net (code "5") (name "A") (class "Default")
      (node (ref "C30") (pin "2") (pinfunction "2_2") (pintype "passive"))
      (node (ref "D11") (pin "2") (pinfunction "A_2") (pintype "passive"))
      (node (ref "D12") (pin "1") (pinfunction "C_1") (pintype "passive"))
      (node (ref "J3") (pin "3_1") (pinfunction "3_3_1") (pintype "passive"))
      (node (ref "J3") (pin "3_2") (pinfunction "3_3_2") (pintype "passive"))
      (node (ref "U10") (pin "4") (pinfunction "HS_4") (pintype "bidirectional"))
      (node (ref "U13") (pin "L1") (pinfunction "L1_L1") (pintype "output"))
      (node (ref "U13") (pin "S1") (pinfunction "S1_S1") (pintype "input"))
    )
    (net (code "6") (name "B") (class "Default")
      (node (ref "C31") (pin "2") (pinfunction "2_2") (pintype "passive"))
      (node (ref "D13") (pin "2") (pinfunction "A_2") (pintype "passive"))
      (node (ref "D14") (pin "1") (pinfunction "C_1") (pintype "passive"))
      (node (ref "J3") (pin "2_1") (pinfunction "2_2_1") (pintype "passive"))
      (node (ref "J3") (pin "2_2") (pinfunction "2_2_2") (pintype "passive"))
      (node (ref "U11") (pin "4") (pinfunction "HS_4") (pintype "bidirectional"))
      (node (ref "U13") (pin "L2") (pinfunction "L2_L2") (pintype "output"))
      (node (ref "U13") (pin "S3") (pinfunction "S3_S3") (pintype "input"))
    )
    (net (code "7") (name "C") (class "Default")
      (node (ref "C32") (pin "2") (pinfunction "2_2") (pintype "passive"))
      (node (ref "D15") (pin "2") (pinfunction "A_2") (pintype "passive"))
      (node (ref "D16") (pin "1") (pinfunction "C_1") (pintype "passive"))
      (node (ref "J3") (pin "1_1") (pinfunction "1_1_1") (pintype "passive"))
      (node (ref "J3") (pin "1_2") (pinfunction "1_1_2") (pintype "passive"))
      (node (ref "U12") (pin "4") (pinfunction "HS_4") (pintype "bidirectional"))
      (node (ref "U13") (pin "L3") (pinfunction "L3_L3") (pintype "output"))
      (node (ref "U13") (pin "S5") (pinfunction "S5_S5") (pintype "input"))
    )
    (net (code "8") (name "DISABLE") (class "Default")
      (node (ref "J2") (pin "4") (pinfunction "4_4") (pintype "bidirectional"))
      (node (ref "R45") (pin "1") (pinfunction "1_1") (pintype "passive"))
      (node (ref "U6") (pin "6") (pinfunction "IO4_6") (pintype "passive"))
    )
    (net (code "9") (name "DISP_OUT") (class "Default")
      (node (ref "J4") (pin "4") (pinfunction "4_4") (pintype "passive"))
      (node (ref "R31") (pin "1") (pinfunction "1_1") (pintype "passive"))
      (node (ref "U8") (pin "6") (pinfunction "IO4_6") (pintype "passive"))
    )
    (net (code "10") (name "FB") (class "Default")
      (node (ref "R11") (pin "1") (pinfunction "1_1") (pintype "passive"))
      (node (ref "R12") (pin "2") (pinfunction "2_2") (pintype "passive"))
      (node (ref "U1") (pin "2") (pinfunction "FB_2") (pintype "input"))
    )
    (net (code "11") (name "GATEDRV") (class "Default")
      (node (ref "R10") (pin "1") (pinfunction "1_1") (pintype "passive"))
      (node (ref "R9") (pin "2") (pinfunction "2_2") (pintype "passive"))
      (node (ref "U1") (pin "5") (pinfunction "GATE_5") (pintype "output"))
    )
    (net (code "12") (name "GH_A") (class "Default")
      (node (ref "R56") (pin "2") (pinfunction "2_2") (pintype "passive"))
      (node (ref "TP17") (pin "P$1") (pinfunction "1_P$1") (pintype "bidirectional"))
      (node (ref "U10") (pin "3") (pinfunction "HO_3") (pintype "output"))
    )
    (net (code "13") (name "GH_B") (class "Default")
      (node (ref "R58") (pin "2") (pinfunction "2_2") (pintype "passive"))
      (node (ref "TP15") (pin "P$1") (pinfunction "1_P$1") (pintype "bidirectional"))
      (node (ref "U11") (pin "3") (pinfunction "HO_3") (pintype "output"))
    )
    (net (code "14") (name "GH_C") (class "Default")
      (node (ref "R60") (pin "2") (pinfunction "2_2") (pintype "passive"))
      (node (ref "TP13") (pin "P$1") (pinfunction "1_P$1") (pintype "bidirectional"))
      (node (ref "U12") (pin "3") (pinfunction "HO_3") (pintype "output"))
    )
    (net (code "15") (name "GL_A") (class "Default")
      (node (ref "R57") (pin "2") (pinfunction "2_2") (pintype "passive"))
      (node (ref "TP16") (pin "P$1") (pinfunction "1_P$1") (pintype "bidirectional"))
      (node (ref "U10") (pin "8") (pinfunction "LO_8") (pintype "output"))
    )
    (net (code "16") (name "GL_B") (class "Default")
      (node (ref "R59") (pin "2") (pinfunction "2_2") (pintype "passive"))
      (node (ref "TP14") (pin "P$1") (pinfunction "1_P$1") (pintype "bidirectional"))
      (node (ref "U11") (pin "8") (pinfunction "LO_8") (pintype "output"))
    )
    (net (code "17") (name "GL_C") (class "Default")
      (node (ref "R61") (pin "2") (pinfunction "2_2") (pintype "passive"))
      (node (ref "TP12") (pin "P$1") (pinfunction "1_P$1") (pintype "bidirectional"))
      (node (ref "U12") (pin "8") (pinfunction "LO_8") (pintype "output"))
    )
    (net (code "18") (name "GND") (class "Default")
      (node (ref "C1") (pin "2") (pinfunction "2_2") (pintype "passive"))
      (node (ref "C11") (pin "C") (pinfunction "-_C") (pintype "passive"))
      (node (ref "C13") (pin "2") (pinfunction "2_2") (pintype "passive"))
      (node (ref "C14") (pin "2") (pinfunction "2_2") (pintype "passive"))
      (node (ref "C15") (pin "2") (pinfunction "2_2") (pintype "passive"))
      (node (ref "C16") (pin "2") (pinfunction "2_2") (pintype "passive"))
      (node (ref "C17") (pin "2") (pinfunction "2_2") (pintype "passive"))
      (node (ref "C18") (pin "2") (pinfunction "2_2") (pintype "passive"))
      (node (ref "C19") (pin "2") (pinfunction "2_2") (pintype "passive"))
      (node (ref "C2") (pin "2") (pinfunction "2_2") (pintype "passive"))
      (node (ref "C20") (pin "2") (pinfunction "2_2") (pintype "passive"))
      (node (ref "C21") (pin "2") (pinfunction "2_2") (pintype "passive"))
      (node (ref "C24") (pin "2") (pinfunction "2_2") (pintype "passive"))
      (node (ref "C26") (pin "2") (pinfunction "2_2") (pintype "passive"))
      (node (ref "C27") (pin "2") (pinfunction "2_2") (pintype "passive"))
      (node (ref "C28") (pin "2") (pinfunction "2_2") (pintype "passive"))
      (node (ref "C29") (pin "2") (pinfunction "2_2") (pintype "passive"))
      (node (ref "C33") (pin "2") (pinfunction "2_2") (pintype "passive"))
      (node (ref "C34") (pin "2") (pinfunction "2_2") (pintype "passive"))
      (node (ref "C5") (pin "2") (pinfunction "2_2") (pintype "passive"))
      (node (ref "C6") (pin "2") (pinfunction "2_2") (pintype "passive"))
      (node (ref "C7") (pin "2") (pinfunction "2_2") (pintype "passive"))
      (node (ref "C8") (pin "2") (pinfunction "2_2") (pintype "passive"))
      (node (ref "C9") (pin "2") (pinfunction "2_2") (pintype "passive"))
      (node (ref "D10") (pin "A") (pinfunction "A_A") (pintype "passive"))
      (node (ref "D12") (pin "2") (pinfunction "A_2") (pintype "passive"))
      (node (ref "D14") (pin "2") (pinfunction "A_2") (pintype "passive"))
      (node (ref "D16") (pin "2") (pinfunction "A_2") (pintype "passive"))
      (node (ref "D3") (pin "A") (pinfunction "A_A") (pintype "passive"))
      (node (ref "D4") (pin "A") (pinfunction "A_A") (pintype "passive"))
      (node (ref "D8") (pin "A") (pinfunction "A_A") (pintype "passive"))
      (node (ref "D9") (pin "A") (pinfunction "A_A") (pintype "passive"))
      (node (ref "J1") (pin "1_1") (pinfunction "1_1_1") (pintype "passive"))
      (node (ref "J1") (pin "1_2") (pinfunction "1_1_2") (pintype "passive"))
      (node (ref "J2") (pin "5") (pinfunction "5_5") (pintype "bidirectional"))
      (node (ref "J4") (pin "6") (pinfunction "6_6") (pintype "passive"))
      (node (ref "J5") (pin "4") (pinfunction "4_4") (pintype "bidirectional"))
      (node (ref "J5") (pin "6") (pinfunction "6_6") (pintype "bidirectional"))
      (node (ref "MOD1") (pin "1") (pinfunction "GND_1") (pintype "power_in"))
      (node (ref "MOD1") (pin "25") (pinfunction "GND_25") (pintype "power_in"))
      (node (ref "MOD1") (pin "51") (pinfunction "GND_51") (pintype "power_in"))
      (node (ref "Q5") (pin "3") (pinfunction "S_3") (pintype "passive"))
      (node (ref "Q6") (pin "3") (pinfunction "S_3") (pintype "passive"))
      (node (ref "R1") (pin "1") (pinfunction "1_1") (pintype "passive"))
      (node (ref "R12") (pin "1") (pinfunction "1_1") (pintype "passive"))
      (node (ref "R13") (pin "1") (pinfunction "1_1") (pintype "passive"))
      (node (ref "R14") (pin "1") (pinfunction "1_1") (pintype "passive"))
      (node (ref "R17") (pin "1") (pinfunction "1_1") (pintype "passive"))
      (node (ref "R19") (pin "1") (pinfunction "1_1") (pintype "passive"))
      (node (ref "R20") (pin "2") (pinfunction "2_2") (pintype "passive"))
      (node (ref "R23") (pin "1") (pinfunction "1_1") (pintype "passive"))
      (node (ref "R24") (pin "2") (pinfunction "2_2") (pintype "passive"))
      (node (ref "R26") (pin "2") (pinfunction "2_2") (pintype "passive"))
      (node (ref "R49") (pin "1") (pinfunction "1_1") (pintype "passive"))
      (node (ref "R53") (pin "2") (pinfunction "2_2") (pintype "passive"))
      (node (ref "R55") (pin "2") (pinfunction "2_2") (pintype "passive"))
      (node (ref "R62") (pin "1") (pinfunction "1_1") (pintype "passive"))
      (node (ref "R7") (pin "1") (pinfunction "1_1") (pintype "passive"))
      (node (ref "SW1") (pin "C1") (pinfunction "C_C1") (pintype "passive"))
      (node (ref "SW1") (pin "C2") (pinfunction "C_C2") (pintype "passive"))
      (node (ref "U1") (pin "12") (pinfunction "GND_12") (pintype "power_in"))
      (node (ref "U10") (pin "7") (pinfunction "VSS_7") (pintype "power_in"))
      (node (ref "U10") (pin "EP1") (pinfunction "VSS_EP1") (pintype "power_in"))
      (node (ref "U10") (pin "EP2") (pinfunction "VSS_EP2") (pintype "power_in"))
      (node (ref "U10") (pin "EP3") (pinfunction "VSS_EP3") (pintype "power_in"))
      (node (ref "U10") (pin "EP4") (pinfunction "VSS_EP4") (pintype "power_in"))
      (node (ref "U10") (pin "EP5") (pinfunction "VSS_EP5") (pintype "power_in"))
      (node (ref "U10") (pin "EP6") (pinfunction "VSS_EP6") (pintype "power_in"))
      (node (ref "U10") (pin "EXP") (pinfunction "VSS_EXP") (pintype "power_in"))
      (node (ref "U11") (pin "7") (pinfunction "VSS_7") (pintype "power_in"))
      (node (ref "U11") (pin "EP1") (pinfunction "VSS_EP1") (pintype "power_in"))
      (node (ref "U11") (pin "EP2") (pinfunction "VSS_EP2") (pintype "power_in"))
      (node (ref "U11") (pin "EP3") (pinfunction "VSS_EP3") (pintype "power_in"))
      (node (ref "U11") (pin "EP4") (pinfunction "VSS_EP4") (pintype "power_in"))
      (node (ref "U11") (pin "EP5") (pinfunction "VSS_EP5") (pintype "power_in"))
      (node (ref "U11") (pin "EP6") (pinfunction "VSS_EP6") (pintype "power_in"))
      (node (ref "U11") (pin "EXP") (pinfunction "VSS_EXP") (pintype "power_in"))
      (node (ref "U12") (pin "7") (pinfunction "VSS_7") (pintype "power_in"))
      (node (ref "U12") (pin "EP1") (pinfunction "VSS_EP1") (pintype "power_in"))
      (node (ref "U12") (pin "EP2") (pinfunction "VSS_EP2") (pintype "power_in"))
      (node (ref "U12") (pin "EP3") (pinfunction "VSS_EP3") (pintype "power_in"))
      (node (ref "U12") (pin "EP4") (pinfunction "VSS_EP4") (pintype "power_in"))
      (node (ref "U12") (pin "EP5") (pinfunction "VSS_EP5") (pintype "power_in"))
      (node (ref "U12") (pin "EP6") (pinfunction "VSS_EP6") (pintype "power_in"))
      (node (ref "U12") (pin "EXP") (pinfunction "VSS_EXP") (pintype "power_in"))
      (node (ref "U13") (pin "L-") (pinfunction "L-_L-") (pintype "power_in"))
      (node (ref "U13") (pin "S2") (pinfunction "S2_S2") (pintype "input"))
      (node (ref "U13") (pin "S4") (pinfunction "S4_S4") (pintype "input"))
      (node (ref "U13") (pin "S6") (pinfunction "S6_S6") (pintype "input"))
      (node (ref "U2") (pin "13") (pinfunction "GND_13") (pintype "power_in"))
      (node (ref "U2") (pin "15") (pinfunction "GND_15") (pintype "power_in"))
      (node (ref "U2") (pin "6") (pinfunction "GND_6") (pintype "power_in"))
      (node (ref "U2") (pin "7") (pinfunction "SYNC/MODE_7") (pintype "input"))
      (node (ref "U2") (pin "9") (pinfunction "GND_9") (pintype "power_in"))
      (node (ref "U2") (pin "EXP") (pinfunction "GND_EXP") (pintype "power_in"))
      (node (ref "U3") (pin "9") (pinfunction "GND_9") (pintype "power_in"))
      (node (ref "U3") (pin "EXP") (pinfunction "GND_EXP") (pintype "power_in"))
      (node (ref "U4") (pin "2") (pinfunction "GND_2") (pintype "power_in"))
      (node (ref "U4") (pin "5") (pinfunction "ADD0_5") (pintype "input"))
      (node (ref "U5") (pin "2") (pinfunction "GND_2") (pintype "power_in"))
      (node (ref "U6") (pin "2") (pinfunction "GND_2") (pintype "power_in"))
      (node (ref "U6") (pin "5") (pinfunction "GND_5") (pintype "power_in"))
      (node (ref "U7") (pin "2") (pinfunction "GND_2") (pintype "power_in"))
      (node (ref "U7") (pin "5") (pinfunction "GND_5") (pintype "power_in"))
      (node (ref "U8") (pin "2") (pinfunction "GND_2") (pintype "power_in"))
      (node (ref "U8") (pin "5") (pinfunction "GND_5") (pintype "power_in"))
      (node (ref "U9") (pin "2") (pinfunction "GND_2") (pintype "power_in"))
      (node (ref "U9") (pin "5") (pinfunction "GND_5") (pintype "power_in"))
    )
    (net (code "19") (name "GPIO_TBD") (class "Default")
      (node (ref "J4") (pin "5") (pinfunction "5_5") (pintype "passive"))
      (node (ref "R41") (pin "1") (pinfunction "1_1") (pintype "passive"))
      (node (ref "U8") (pin "4") (pinfunction "IO3_4") (pintype "passive"))
    )
    (net (code "20") (name "H1") (class "Default")
      (node (ref "C22") (pin "2") (pinfunction "2_2") (pintype "passive"))
      (node (ref "J5") (pin "1") (pinfunction "1_1") (pintype "bidirectional"))
      (node (ref "R38") (pin "1") (pinfunction "1_1") (pintype "passive"))
      (node (ref "R50") (pin "2") (pinfunction "2_2") (pintype "passive"))
      (node (ref "TP6") (pin "P$1") (pinfunction "1_P$1") (pintype "bidirectional"))
      (node (ref "U9") (pin "3") (pinfunction "IO2_3") (pintype "passive"))
    )
    (net (code "21") (name "H2") (class "Default")
      (node (ref "C23") (pin "2") (pinfunction "2_2") (pintype "passive"))
      (node (ref "J5") (pin "2") (pinfunction "2_2") (pintype "bidirectional"))
      (node (ref "R39") (pin "1") (pinfunction "1_1") (pintype "passive"))
      (node (ref "R51") (pin "2") (pinfunction "2_2") (pintype "passive"))
      (node (ref "TP7") (pin "P$1") (pinfunction "1_P$1") (pintype "bidirectional"))
      (node (ref "U9") (pin "4") (pinfunction "IO3_4") (pintype "passive"))
    )
    (net (code "22") (name "H3") (class "Default")
      (node (ref "C25") (pin "2") (pinfunction "2_2") (pintype "passive"))
      (node (ref "J5") (pin "3") (pinfunction "3_3") (pintype "bidirectional"))
      (node (ref "R40") (pin "1") (pinfunction "1_1") (pintype "passive"))
      (node (ref "R52") (pin "2") (pinfunction "2_2") (pintype "passive"))
      (node (ref "TP8") (pin "P$1") (pinfunction "1_P$1") (pintype "bidirectional"))
      (node (ref "U9") (pin "6") (pinfunction "IO4_6") (pintype "passive"))
    )
    (net (code "23") (name "INH_A") (class "Default")
      (node (ref "MOD1") (pin "39") (pinfunction "P12_3_39") (pintype "bidirectional"))
      (node (ref "U10") (pin "5") (pinfunction "HI_5") (pintype "input"))
    )
    (net (code "24") (name "INH_B") (class "Default")
      (node (ref "MOD1") (pin "37") (pinfunction "P12_5_37") (pintype "bidirectional"))
      (node (ref "U11") (pin "5") (pinfunction "HI_5") (pintype "input"))
    )
    (net (code "25") (name "INH_C") (class "Default")
      (node (ref "MOD1") (pin "35") (pinfunction "P12_7_35") (pintype "bidirectional"))
      (node (ref "U12") (pin "5") (pinfunction "HI_5") (pintype "input"))
    )
    (net (code "26") (name "INL_A") (class "Default")
      (node (ref "MOD1") (pin "38") (pinfunction "P12_4_38") (pintype "bidirectional"))
      (node (ref "U10") (pin "6") (pinfunction "LI_6") (pintype "input"))
    )
    (net (code "27") (name "INL_B") (class "Default")
      (node (ref "MOD1") (pin "36") (pinfunction "P12_6_36") (pintype "bidirectional"))
      (node (ref "U11") (pin "6") (pinfunction "LI_6") (pintype "input"))
    )
    (net (code "28") (name "INL_C") (class "Default")
      (node (ref "MOD1") (pin "34") (pinfunction "P2_7_34") (pintype "bidirectional"))
      (node (ref "U12") (pin "6") (pinfunction "LI_6") (pintype "input"))
    )
    (net (code "29") (name "ISENSE") (class "Default")
      (node (ref "C24") (pin "1") (pinfunction "1_1") (pintype "passive"))
      (node (ref "MOD1") (pin "21") (pinfunction "P0_5_21") (pintype "bidirectional"))
      (node (ref "TP10") (pin "P$1") (pinfunction "1_P$1") (pintype "bidirectional"))
      (node (ref "U5") (pin "3") (pinfunction "VIOUT_3") (pintype "output"))
      (node (ref "U7") (pin "4") (pinfunction "IO3_4") (pintype "passive"))
    )
    (net (code "30") (name "MODESET1") (class "Default")
      (node (ref "R34") (pin "1") (pinfunction "1_1") (pintype "passive"))
      (node (ref "SW1") (pin "1") (pinfunction "1_1") (pintype "passive"))
    )
    (net (code "31") (name "MODESET2") (class "Default")
      (node (ref "R35") (pin "1") (pinfunction "1_1") (pintype "passive"))
      (node (ref "SW1") (pin "2") (pinfunction "2_2") (pintype "passive"))
    )
    (net (code "32") (name "MODESET3") (class "Default")
      (node (ref "R36") (pin "1") (pinfunction "1_1") (pintype "passive"))
      (node (ref "SW1") (pin "4") (pinfunction "4_4") (pintype "passive"))
    )
    (net (code "33") (name "MODESET4") (class "Default")
      (node (ref "R37") (pin "1") (pinfunction "1_1") (pintype "passive"))
      (node (ref "SW1") (pin "8") (pinfunction "8_8") (pintype "passive"))
    )
    (net (code "34") (name "MONITOR_RX") (class "Default")
      (node (ref "J4") (pin "3") (pinfunction "3_3") (pintype "passive"))
      (node (ref "R30") (pin "1") (pinfunction "1_1") (pintype "passive"))
      (node (ref "U8") (pin "1") (pinfunction "IO1_1") (pintype "passive"))
    )
    (net (code "35") (name "MONITOR_TX") (class "Default")
      (node (ref "J4") (pin "2") (pinfunction "2_2") (pintype "passive"))
      (node (ref "R29") (pin "1") (pinfunction "1_1") (pintype "passive"))
      (node (ref "U8") (pin "3") (pinfunction "IO2_3") (pintype "passive"))
    )
    (net (code "36") (name "Net-(C3-Pad2)") (class "Default")
      (node (ref "C3") (pin "2") (pinfunction "2_2") (pintype "passive"))
      (node (ref "R13") (pin "2") (pinfunction "2_2") (pintype "passive"))
    )
    (net (code "37") (name "Net-(C4-Pad2)") (class "Default")
      (node (ref "C4") (pin "2") (pinfunction "2_2") (pintype "passive"))
      (node (ref "R14") (pin "2") (pinfunction "2_2") (pintype "passive"))
    )
    (net (code "38") (name "Net-(C6-Pad1)") (class "Default")
      (node (ref "C6") (pin "1") (pinfunction "1_1") (pintype "passive"))
      (node (ref "R15") (pin "2") (pinfunction "2_2") (pintype "passive"))
      (node (ref "U3") (pin "1") (pinfunction "IN_1") (pintype "power_in"))
      (node (ref "U3") (pin "2") (pinfunction "IN_2") (pintype "power_in"))
      (node (ref "U3") (pin "3") (pinfunction "IN_3") (pintype "power_in"))
    )
    (net (code "39") (name "Net-(C11-+)") (class "Default")
      (node (ref "C11") (pin "A") (pinfunction "+_A") (pintype "passive"))
      (node (ref "R24") (pin "1") (pinfunction "1_1") (pintype "passive"))
      (node (ref "U3") (pin "8") (pinfunction "SET_8") (pintype "output"))
    )
    (net (code "40") (name "Net-(C33-Pad1)") (class "Default")
      (node (ref "C33") (pin "1") (pinfunction "1_1") (pintype "passive"))
      (node (ref "F2") (pin "1") (pinfunction "1_1") (pintype "bidirectional"))
      (node (ref "J5") (pin "5") (pinfunction "5_5") (pintype "bidirectional"))
    )
    (net (code "41") (name "Net-(D1-PadA)") (class "Default")
      (node (ref "D1") (pin "A") (pinfunction "A_A") (pintype "passive"))
      (node (ref "Q1") (pin "2") (pinfunction "D_2") (pintype "passive"))
      (node (ref "Q1") (pin "4") (pinfunction "D_4") (pintype "passive"))
    )
    (net (code "42") (name "Net-(D1-PadC)") (class "Default")
      (node (ref "D1") (pin "C") (pinfunction "C_C") (pintype "passive"))
      (node (ref "R1") (pin "2") (pinfunction "2_2") (pintype "passive"))
    )
    (net (code "43") (name "Net-(D3-PadC)") (class "Default")
      (node (ref "D3") (pin "C") (pinfunction "C_C") (pintype "passive"))
      (node (ref "R4") (pin "1") (pinfunction "1_1") (pintype "passive"))
    )
    (net (code "44") (name "Net-(D5-PadA)") (class "Default")
      (node (ref "D5") (pin "A") (pinfunction "A_A") (pintype "passive"))
      (node (ref "R27") (pin "1") (pinfunction "1_1") (pintype "passive"))
    )
    (net (code "45") (name "Net-(D5-PadC)") (class "Default")
      (node (ref "D5") (pin "C") (pinfunction "C_C") (pintype "passive"))
      (node (ref "Q5") (pin "2") (pinfunction "D_2") (pintype "passive"))
      (node (ref "Q5") (pin "4") (pinfunction "D_4") (pintype "passive"))
    )
    (net (code "46") (name "Net-(D6-PadA)") (class "Default")
      (node (ref "D6") (pin "A") (pinfunction "A_A") (pintype "passive"))
      (node (ref "R28") (pin "1") (pinfunction "1_1") (pintype "passive"))
    )
    (net (code "47") (name "Net-(D6-PadC)") (class "Default")
      (node (ref "D6") (pin "C") (pinfunction "C_C") (pintype "passive"))
      (node (ref "Q6") (pin "2") (pinfunction "D_2") (pintype "passive"))
      (node (ref "Q6") (pin "4") (pinfunction "D_4") (pintype "passive"))
    )
    (net (code "48") (name "Net-(D7-BLUE)") (class "Default")
      (node (ref "D7") (pin "3") (pinfunction "BLUE_3") (pintype "passive"))
      (node (ref "R44") (pin "2") (pinfunction "2_2") (pintype "passive"))
    )
    (net (code "49") (name "Net-(D7-GREEN)") (class "Default")
      (node (ref "D7") (pin "4") (pinfunction "GREEN_4") (pintype "passive"))
      (node (ref "R43") (pin "2") (pinfunction "2_2") (pintype "passive"))
    )
    (net (code "50") (name "Net-(D7-RED)") (class "Default")
      (node (ref "D7") (pin "1") (pinfunction "RED_1") (pintype "passive"))
      (node (ref "R42") (pin "2") (pinfunction "2_2") (pintype "passive"))
    )
    (net (code "51") (name "Net-(F1-Pad2)") (class "Default")
      (node (ref "F1") (pin "2") (pinfunction "2_2") (pintype "bidirectional"))
      (node (ref "J4") (pin "1") (pinfunction "1_1") (pintype "passive"))
    )
    (net (code "52") (name "Net-(L1-1)") (class "Default")
      (node (ref "C10") (pin "2") (pinfunction "2_2") (pintype "passive"))
      (node (ref "L1") (pin "P$1") (pinfunction "1_P$1") (pintype "passive"))
      (node (ref "U2") (pin "20") (pinfunction "SW_20") (pintype "passive"))
    )
    (net (code "53") (name "Net-(L1-2)") (class "Default")
      (node (ref "L1") (pin "P$2") (pinfunction "2_P$2") (pintype "passive"))
      (node (ref "U2") (pin "14") (pinfunction "IND_14") (pintype "passive"))
    )
    (net (code "54") (name "Net-(MOD1-P1_4)") (class "Default")
      (node (ref "MOD1") (pin "47") (pinfunction "P1_4_47") (pintype "bidirectional"))
      (node (ref "R29") (pin "2") (pinfunction "2_2") (pintype "passive"))
    )
    (net (code "55") (name "Net-(MOD1-P1_5)") (class "Default")
      (node (ref "MOD1") (pin "48") (pinfunction "P1_5_48") (pintype "bidirectional"))
      (node (ref "R30") (pin "2") (pinfunction "2_2") (pintype "passive"))
    )
    (net (code "56") (name "Net-(MOD1-P1_7)") (class "Default")
      (node (ref "MOD1") (pin "50") (pinfunction "P1_7_50") (pintype "bidirectional"))
      (node (ref "R31") (pin "2") (pinfunction "2_2") (pintype "passive"))
    )
    (net (code "57") (name "Net-(MOD1-P2_0)") (class "Default")
      (node (ref "MOD1") (pin "27") (pinfunction "P2_0_27") (pintype "bidirectional"))
      (node (ref "R32") (pin "2") (pinfunction "2_2") (pintype "passive"))
    )
    (net (code "58") (name "Net-(MOD1-P2_3)") (class "Default")
      (node (ref "MOD1") (pin "30") (pinfunction "P2_3_30") (pintype "bidirectional"))
      (node (ref "R41") (pin "2") (pinfunction "2_2") (pintype "passive"))
    )
    (net (code "59") (name "Net-(MOD1-P2_4)") (class "Default")
      (node (ref "MOD1") (pin "31") (pinfunction "P2_4_31") (pintype "bidirectional"))
      (node (ref "R42") (pin "1") (pinfunction "1_1") (pintype "passive"))
    )
    (net (code "60") (name "Net-(MOD1-P2_5)") (class "Default")
      (node (ref "MOD1") (pin "32") (pinfunction "P2_5_32") (pintype "bidirectional"))
      (node (ref "R43") (pin "1") (pinfunction "1_1") (pintype "passive"))
    )
    (net (code "61") (name "Net-(MOD1-P2_6)") (class "Default")
      (node (ref "MOD1") (pin "33") (pinfunction "P2_6_33") (pintype "bidirectional"))
      (node (ref "R44") (pin "1") (pinfunction "1_1") (pintype "passive"))
    )
    (net (code "62") (name "Net-(MOD1-P3_0)") (class "Default")
      (node (ref "MOD1") (pin "2") (pinfunction "P3_0_2") (pintype "bidirectional"))
      (node (ref "R34") (pin "2") (pinfunction "2_2") (pintype "passive"))
    )
    (net (code "63") (name "Net-(MOD1-P3_1)") (class "Default")
      (node (ref "MOD1") (pin "3") (pinfunction "P3_1_3") (pintype "bidirectional"))
      (node (ref "R35") (pin "2") (pinfunction "2_2") (pintype "passive"))
    )
    (net (code "64") (name "Net-(MOD1-P3_3)") (class "Default")
      (node (ref "MOD1") (pin "5") (pinfunction "P3_3_5") (pintype "bidirectional"))
      (node (ref "R36") (pin "2") (pinfunction "2_2") (pintype "passive"))
    )
    (net (code "65") (name "Net-(MOD1-P3_4)") (class "Default")
      (node (ref "MOD1") (pin "6") (pinfunction "P3_4_6") (pintype "bidirectional"))
      (node (ref "R37") (pin "2") (pinfunction "2_2") (pintype "passive"))
    )
    (net (code "66") (name "Net-(MOD1-P3_5)") (class "Default")
      (node (ref "C21") (pin "1") (pinfunction "1_1") (pintype "passive"))
      (node (ref "MOD1") (pin "7") (pinfunction "P3_5_7") (pintype "bidirectional"))
      (node (ref "R47") (pin "2") (pinfunction "2_2") (pintype "passive"))
      (node (ref "TP11") (pin "P$1") (pinfunction "1_P$1") (pintype "bidirectional"))
    )
    (net (code "67") (name "Net-(MOD1-P12_0)") (class "Default")
      (node (ref "MOD1") (pin "42") (pinfunction "P12_0_42") (pintype "bidirectional"))
      (node (ref "R38") (pin "2") (pinfunction "2_2") (pintype "passive"))
    )
    (net (code "68") (name "Net-(MOD1-P12_1)") (class "Default")
      (node (ref "MOD1") (pin "41") (pinfunction "P12_1_41") (pintype "bidirectional"))
      (node (ref "R39") (pin "2") (pinfunction "2_2") (pintype "passive"))
    )
    (net (code "69") (name "Net-(MOD1-P12_2)") (class "Default")
      (node (ref "MOD1") (pin "40") (pinfunction "P12_2_40") (pintype "bidirectional"))
      (node (ref "R40") (pin "2") (pinfunction "2_2") (pintype "passive"))
    )
    (net (code "70") (name "Net-(MOD1-P15_3)") (class "Default")
      (node (ref "MOD1") (pin "13") (pinfunction "P15_3_13") (pintype "bidirectional"))
      (node (ref "R45") (pin "2") (pinfunction "2_2") (pintype "passive"))
    )
    (net (code "71") (name "Net-(Q1-G)") (class "Default")
      (node (ref "Q1") (pin "1") (pinfunction "G_1") (pintype "passive"))
      (node (ref "R2") (pin "1") (pinfunction "1_1") (pintype "passive"))
      (node (ref "R3") (pin "1") (pinfunction "1_1") (pintype "passive"))
    )
    (net (code "72") (name "Net-(Q2-B)") (class "Default")
      (node (ref "D2") (pin "C") (pinfunction "C_C") (pintype "passive"))
      (node (ref "Q2") (pin "1") (pinfunction "B_1") (pintype "passive"))
      (node (ref "R4") (pin "2") (pinfunction "2_2") (pintype "passive"))
    )
    (net (code "73") (name "Net-(Q2-C)") (class "Default")
      (node (ref "Q2") (pin "3") (pinfunction "C_3") (pintype "passive"))
      (node (ref "R5") (pin "1") (pinfunction "1_1") (pintype "passive"))
      (node (ref "R9") (pin "1") (pinfunction "1_1") (pintype "passive"))
    )
    (net (code "74") (name "Net-(Q3-G)") (class "Default")
      (node (ref "Q3") (pin "1") (pinfunction "G_1") (pintype "passive"))
      (node (ref "R5") (pin "2") (pinfunction "2_2") (pintype "passive"))
    )
    (net (code "75") (name "Net-(Q4-G)") (class "Default")
      (node (ref "Q4") (pin "1") (pinfunction "G_1") (pintype "passive"))
      (node (ref "R10") (pin "2") (pinfunction "2_2") (pintype "passive"))
    )
    (net (code "76") (name "Net-(R56-Pad1)") (class "Default")
      (node (ref "R56") (pin "1") (pinfunction "1_1") (pintype "passive"))
      (node (ref "U13") (pin "G1") (pinfunction "G1_G1") (pintype "input"))
    )
    (net (code "77") (name "Net-(R57-Pad1)") (class "Default")
      (node (ref "R57") (pin "1") (pinfunction "1_1") (pintype "passive"))
      (node (ref "U13") (pin "G2") (pinfunction "G2_G2") (pintype "input"))
    )
    (net (code "78") (name "Net-(R58-Pad1)") (class "Default")
      (node (ref "R58") (pin "1") (pinfunction "1_1") (pintype "passive"))
      (node (ref "U13") (pin "G3") (pinfunction "G3_G3") (pintype "input"))
    )
    (net (code "79") (name "Net-(R59-Pad1)") (class "Default")
      (node (ref "R59") (pin "1") (pinfunction "1_1") (pintype "passive"))
      (node (ref "U13") (pin "G4") (pinfunction "G4_G4") (pintype "input"))
    )
    (net (code "80") (name "Net-(R60-Pad1)") (class "Default")
      (node (ref "R60") (pin "1") (pinfunction "1_1") (pintype "passive"))
      (node (ref "U13") (pin "G5") (pinfunction "G5_G5") (pintype "input"))
    )
    (net (code "81") (name "Net-(R61-Pad1)") (class "Default")
      (node (ref "R61") (pin "1") (pinfunction "1_1") (pintype "passive"))
      (node (ref "U13") (pin "G6") (pinfunction "G6_G6") (pintype "input"))
    )
    (net (code "82") (name "Net-(S1-P$1)") (class "Default")
      (node (ref "C34") (pin "1") (pinfunction "1_1") (pintype "passive"))
      (node (ref "R62") (pin "2") (pinfunction "2_2") (pintype "passive"))
      (node (ref "S1") (pin "P1") (pinfunction "P$1_P1") (pintype "bidirectional"))
    )
    (net (code "83") (name "Net-(U1-IN+)") (class "Default")
      (node (ref "R6") (pin "1") (pinfunction "1_1") (pintype "passive"))
      (node (ref "R7") (pin "2") (pinfunction "2_2") (pintype "passive"))
      (node (ref "U1") (pin "16") (pinfunction "IN+_16") (pintype "input"))
    )
    (net (code "84") (name "Net-(U1-TMR)") (class "Default")
      (node (ref "C2") (pin "1") (pinfunction "1_1") (pintype "passive"))
      (node (ref "U1") (pin "1") (pinfunction "TMR_1") (pintype "bidirectional"))
    )
    (net (code "85") (name "Net-(U2-BST)") (class "Default")
      (node (ref "C10") (pin "1") (pinfunction "1_1") (pintype "passive"))
      (node (ref "U2") (pin "18") (pinfunction "BST_18") (pintype "passive"))
    )
    (net (code "86") (name "Net-(U2-EN{slash}UV)") (class "Default")
      (node (ref "C7") (pin "1") (pinfunction "1_1") (pintype "passive"))
      (node (ref "R16") (pin "1") (pinfunction "1_1") (pintype "passive"))
      (node (ref "R17") (pin "2") (pinfunction "2_2") (pintype "passive"))
      (node (ref "U2") (pin "3") (pinfunction "EN/UV_3") (pintype "input"))
    )
    (net (code "87") (name "Net-(U2-FB)") (class "Default")
      (node (ref "C12") (pin "2") (pinfunction "2_2") (pintype "passive"))
      (node (ref "C13") (pin "1") (pinfunction "1_1") (pintype "passive"))
      (node (ref "R22") (pin "1") (pinfunction "1_1") (pintype "passive"))
      (node (ref "R23") (pin "2") (pinfunction "2_2") (pintype "passive"))
      (node (ref "U2") (pin "11") (pinfunction "FB_11") (pintype "input"))
    )
    (net (code "88") (name "Net-(U2-INTVCC)") (class "Default")
      (node (ref "C8") (pin "1") (pinfunction "1_1") (pintype "passive"))
      (node (ref "U2") (pin "16") (pinfunction "INTVCC_16") (pintype "passive"))
    )
    (net (code "89") (name "Net-(U2-RT)") (class "Default")
      (node (ref "R19") (pin "2") (pinfunction "2_2") (pintype "passive"))
      (node (ref "U2") (pin "8") (pinfunction "RT_8") (pintype "passive"))
    )
    (net (code "90") (name "Net-(U2-TR{slash}SS)") (class "Default")
      (node (ref "C9") (pin "1") (pinfunction "1_1") (pintype "passive"))
      (node (ref "U2") (pin "10") (pinfunction "TR/SS_10") (pintype "passive"))
    )
    (net (code "91") (name "Net-(U3-ILIM)") (class "Default")
      (node (ref "R20") (pin "1") (pinfunction "1_1") (pintype "passive"))
      (node (ref "U3") (pin "6") (pinfunction "ILIM_6") (pintype "output"))
    )
    (net (code "92") (name "Net-(U10-HB)") (class "Default")
      (node (ref "C30") (pin "1") (pinfunction "1_1") (pintype "passive"))
      (node (ref "U10") (pin "2") (pinfunction "HB_2") (pintype "output"))
    )
    (net (code "93") (name "Net-(U11-HB)") (class "Default")
      (node (ref "C31") (pin "1") (pinfunction "1_1") (pintype "passive"))
      (node (ref "U11") (pin "2") (pinfunction "HB_2") (pintype "output"))
    )
    (net (code "94") (name "Net-(U12-HB)") (class "Default")
      (node (ref "C32") (pin "1") (pinfunction "1_1") (pintype "passive"))
      (node (ref "U12") (pin "2") (pinfunction "HB_2") (pintype "output"))
    )
    (net (code "95") (name "PG_FB") (class "Default")
      (node (ref "R25") (pin "2") (pinfunction "2_2") (pintype "passive"))
      (node (ref "R26") (pin "1") (pinfunction "1_1") (pintype "passive"))
      (node (ref "U3") (pin "7") (pinfunction "PGFB_7") (pintype "input"))
    )
    (net (code "96") (name "POST-SENSE") (class "Default")
      (node (ref "Q4") (pin "4") (pinfunction "D_4") (pintype "passive"))
      (node (ref "R8") (pin "2") (pinfunction "2_2") (pintype "passive"))
      (node (ref "U1") (pin "7") (pinfunction "SNS_7") (pintype "input"))
    )
    (net (code "97") (name "PRE-SENSE") (class "Default")
      (node (ref "D4") (pin "C") (pinfunction "C_C") (pintype "passive"))
      (node (ref "Q1") (pin "3") (pinfunction "S_3") (pintype "passive"))
      (node (ref "Q3") (pin "4") (pinfunction "D_4") (pintype "passive"))
      (node (ref "R2") (pin "2") (pinfunction "2_2") (pintype "passive"))
      (node (ref "R6") (pin "2") (pinfunction "2_2") (pintype "passive"))
      (node (ref "R8") (pin "1") (pinfunction "1_1") (pintype "passive"))
      (node (ref "U1") (pin "8") (pinfunction "VCC_8") (pintype "power_in"))
      (node (ref "U1") (pin "9") (pinfunction "~{SHDN}_9") (pintype "input"))
    )
    (net (code "98") (name "REVERSE") (class "Default")
      (node (ref "J2") (pin "6") (pinfunction "6_6") (pintype "bidirectional"))
      (node (ref "R32") (pin "1") (pinfunction "1_1") (pintype "passive"))
      (node (ref "U6") (pin "3") (pinfunction "IO2_3") (pintype "passive"))
    )
    (net (code "99") (name "SCL") (class "Default")
      (node (ref "MOD1") (pin "11") (pinfunction "P15_1_11") (pintype "bidirectional"))
      (node (ref "R33") (pin "2") (pinfunction "2_2") (pintype "passive"))
      (node (ref "TP4") (pin "P$1") (pinfunction "1_P$1") (pintype "bidirectional"))
      (node (ref "U4") (pin "1") (pinfunction "SCL_1") (pintype "bidirectional"))
    )
    (net (code "100") (name "SDA") (class "Default")
      (node (ref "MOD1") (pin "10") (pinfunction "P15_0_10") (pintype "bidirectional"))
      (node (ref "R46") (pin "2") (pinfunction "2_2") (pintype "passive"))
      (node (ref "TP5") (pin "P$1") (pinfunction "1_P$1") (pintype "bidirectional"))
      (node (ref "U4") (pin "6") (pinfunction "SDA_6") (pintype "bidirectional"))
    )
    (net (code "101") (name "THROTTLE_1") (class "Default")
      (node (ref "J2") (pin "1") (pinfunction "1_1") (pintype "bidirectional"))
      (node (ref "R54") (pin "2") (pinfunction "2_2") (pintype "passive"))
      (node (ref "U6") (pin "1") (pinfunction "IO1_1") (pintype "passive"))
    )
    (net (code "102") (name "THROTTLE_2") (class "Default")
      (node (ref "J2") (pin "2") (pinfunction "2_2") (pintype "bidirectional"))
      (node (ref "R47") (pin "1") (pinfunction "1_1") (pintype "passive"))
      (node (ref "R53") (pin "1") (pinfunction "1_1") (pintype "passive"))
      (node (ref "U6") (pin "4") (pinfunction "IO3_4") (pintype "passive"))
    )
    (net (code "103") (name "THROTTLE_3") (class "Default")
      (node (ref "J2") (pin "3") (pinfunction "3_3") (pintype "bidirectional"))
      (node (ref "R55") (pin "1") (pinfunction "1_1") (pintype "passive"))
    )
    (net (code "104") (name "T_ALERT") (class "Default")
      (node (ref "MOD1") (pin "12") (pinfunction "P15_2_12") (pintype "bidirectional"))
      (node (ref "U4") (pin "3") (pinfunction "ALERT_3") (pintype "output"))
    )
    (net (code "105") (name "UNDERVOLTAGE") (class "Default")
      (node (ref "R3") (pin "2") (pinfunction "2_2") (pintype "passive"))
      (node (ref "U1") (pin "14") (pinfunction "AOUT_14") (pintype "output"))
    )
    (net (code "106") (name "VCC") (class "Default")
      (node (ref "C1") (pin "1") (pinfunction "1_1") (pintype "passive"))
      (node (ref "C3") (pin "1") (pinfunction "1_1") (pintype "passive"))
      (node (ref "C4") (pin "1") (pinfunction "1_1") (pintype "passive"))
      (node (ref "C5") (pin "1") (pinfunction "1_1") (pintype "passive"))
      (node (ref "Q4") (pin "3") (pinfunction "S_3") (pintype "passive"))
      (node (ref "R11") (pin "2") (pinfunction "2_2") (pintype "passive"))
      (node (ref "R16") (pin "2") (pinfunction "2_2") (pintype "passive"))
      (node (ref "R48") (pin "2") (pinfunction "2_2") (pintype "passive"))
      (node (ref "TP1") (pin "P$1") (pinfunction "1_P$1") (pintype "bidirectional"))
      (node (ref "U1") (pin "4") (pinfunction "OUT_4") (pintype "input"))
      (node (ref "U2") (pin "1") (pinfunction "VIN_1") (pintype "power_in"))
    )
    (net (code "107") (name "VIN") (class "Default")
      (node (ref "J1") (pin "2_1") (pinfunction "2_2_1") (pintype "passive"))
      (node (ref "J1") (pin "2_2") (pinfunction "2_2_2") (pintype "passive"))
      (node (ref "U5") (pin "4_1") (pinfunction "IP+_4_1") (pintype "passive"))
      (node (ref "U5") (pin "4_2") (pinfunction "IP+_4_2") (pintype "passive"))
      (node (ref "U5") (pin "4_3") (pinfunction "IP+_4_3") (pintype "passive"))
      (node (ref "U5") (pin "4_4") (pinfunction "IP+_4_4") (pintype "passive"))
      (node (ref "U5") (pin "4_5") (pinfunction "IP+_4_5") (pintype "passive"))
      (node (ref "U5") (pin "4_6") (pinfunction "IP+_4_6") (pintype "passive"))
      (node (ref "U5") (pin "4_7") (pinfunction "IP+_4_7") (pintype "passive"))
      (node (ref "U5") (pin "4_8") (pinfunction "IP+_4_8") (pintype "passive"))
    )
    (net (code "108") (name "VSENSE") (class "Default")
      (node (ref "MOD1") (pin "17") (pinfunction "P0_1_17") (pintype "bidirectional"))
      (node (ref "R48") (pin "1") (pinfunction "1_1") (pintype "passive"))
      (node (ref "R49") (pin "2") (pinfunction "2_2") (pintype "passive"))
      (node (ref "TP9") (pin "P$1") (pinfunction "1_P$1") (pintype "bidirectional"))
      (node (ref "U7") (pin "3") (pinfunction "IO2_3") (pintype "passive"))
    )
    (net (code "109") (name "V_BATT") (class "Default")
      (node (ref "D11") (pin "1") (pinfunction "C_1") (pintype "passive"))
      (node (ref "D13") (pin "1") (pinfunction "C_1") (pintype "passive"))
      (node (ref "D15") (pin "1") (pinfunction "C_1") (pintype "passive"))
      (node (ref "D2") (pin "A") (pinfunction "A_A") (pintype "passive"))
      (node (ref "Q2") (pin "2") (pinfunction "E_2") (pintype "passive"))
      (node (ref "Q3") (pin "3") (pinfunction "S_3") (pintype "passive"))
      (node (ref "U13") (pin "L+") (pinfunction "L+_L+") (pintype "power_in"))
      (node (ref "U5") (pin "5_1") (pinfunction "IP-_5_1") (pintype "passive"))
      (node (ref "U5") (pin "5_2") (pinfunction "IP-_5_2") (pintype "passive"))
      (node (ref "U5") (pin "5_3") (pinfunction "IP-_5_3") (pintype "passive"))
      (node (ref "U5") (pin "5_4") (pinfunction "IP-_5_4") (pintype "passive"))
      (node (ref "U5") (pin "5_5") (pinfunction "IP-_5_5") (pintype "passive"))
      (node (ref "U5") (pin "5_6") (pinfunction "IP-_5_6") (pintype "passive"))
      (node (ref "U5") (pin "5_7") (pinfunction "IP-_5_7") (pintype "passive"))
      (node (ref "U5") (pin "5_8") (pinfunction "IP-_5_8") (pintype "passive"))
    )
    (net (code "110") (name "unconnected-(MOD1-P0_0-Pad16)") (class "Default")
      (node (ref "MOD1") (pin "16") (pinfunction "P0_0_16") (pintype "bidirectional"))
    )
    (net (code "111") (name "unconnected-(MOD1-P0_2-Pad18)") (class "Default")
      (node (ref "MOD1") (pin "18") (pinfunction "P0_2_18") (pintype "bidirectional"))
    )
    (net (code "112") (name "unconnected-(MOD1-P0_3-Pad19)") (class "Default")
      (node (ref "MOD1") (pin "19") (pinfunction "P0_3_19") (pintype "bidirectional"))
    )
    (net (code "113") (name "unconnected-(MOD1-P0_4-Pad20)") (class "Default")
      (node (ref "MOD1") (pin "20") (pinfunction "P0_4_20") (pintype "bidirectional"))
    )
    (net (code "114") (name "unconnected-(MOD1-P0_6-Pad22)") (class "Default")
      (node (ref "MOD1") (pin "22") (pinfunction "P0_6_22") (pintype "bidirectional"))
    )
    (net (code "115") (name "unconnected-(MOD1-P0_7-Pad23)") (class "Default")
      (node (ref "MOD1") (pin "23") (pinfunction "P0_7_23") (pintype "bidirectional"))
    )
    (net (code "116") (name "unconnected-(MOD1-P1_0-Pad43)") (class "Default")
      (node (ref "MOD1") (pin "43") (pinfunction "P1_0_43") (pintype "bidirectional"))
    )
    (net (code "117") (name "unconnected-(MOD1-P1_1-Pad44)") (class "Default")
      (node (ref "MOD1") (pin "44") (pinfunction "P1_1_44") (pintype "bidirectional"))
    )
    (net (code "118") (name "unconnected-(MOD1-P1_2-Pad45)") (class "Default")
      (node (ref "MOD1") (pin "45") (pinfunction "P1_2_45") (pintype "bidirectional"))
    )
    (net (code "119") (name "unconnected-(MOD1-P1_3-Pad46)") (class "Default")
      (node (ref "MOD1") (pin "46") (pinfunction "P1_3_46") (pintype "bidirectional"))
    )
    (net (code "120") (name "unconnected-(MOD1-P2_1-Pad28)") (class "Default")
      (node (ref "MOD1") (pin "28") (pinfunction "P2_1_28") (pintype "bidirectional"))
    )
    (net (code "121") (name "unconnected-(MOD1-P2_2-Pad29)") (class "Default")
      (node (ref "MOD1") (pin "29") (pinfunction "P2_2_29") (pintype "bidirectional"))
    )
    (net (code "122") (name "unconnected-(MOD1-P3_2-Pad4)") (class "Default")
      (node (ref "MOD1") (pin "4") (pinfunction "P3_2_4") (pintype "bidirectional"))
    )
    (net (code "123") (name "unconnected-(MOD1-P3_6-Pad8)") (class "Default")
      (node (ref "MOD1") (pin "8") (pinfunction "P3_6_8") (pintype "bidirectional"))
    )
    (net (code "124") (name "unconnected-(MOD1-P3_7-Pad9)") (class "Default")
      (node (ref "MOD1") (pin "9") (pinfunction "P3_7_9") (pintype "bidirectional"))
    )
    (net (code "125") (name "unconnected-(MOD1-P15_4-Pad14)") (class "Default")
      (node (ref "MOD1") (pin "14") (pinfunction "P15_4_14") (pintype "bidirectional"))
    )
    (net (code "126") (name "unconnected-(MOD1-P15_5-Pad15)") (class "Default")
      (node (ref "MOD1") (pin "15") (pinfunction "P15_5_15") (pintype "bidirectional"))
    )
    (net (code "127") (name "unconnected-(MOD1-P_XRES-Pad24)") (class "Default")
      (node (ref "MOD1") (pin "24") (pinfunction "P_XRES_24") (pintype "bidirectional"))
    )
    (net (code "128") (name "unconnected-(S2-P$1-PadP1)") (class "Default")
      (node (ref "S2") (pin "P1") (pinfunction "P$1_P1") (pintype "bidirectional"))
    )
    (net (code "129") (name "unconnected-(S3-P$1-PadP1)") (class "Default")
      (node (ref "S3") (pin "P1") (pinfunction "P$1_P1") (pintype "bidirectional"))
    )
    (net (code "130") (name "unconnected-(S4-P$1-PadP1)") (class "Default")
      (node (ref "S4") (pin "P1") (pinfunction "P$1_P1") (pintype "bidirectional"))
    )
    (net (code "131") (name "unconnected-(U1-EN-Pad11)") (class "Default")
      (node (ref "U1") (pin "11") (pinfunction "EN_11") (pintype "output"))
    )
    (net (code "132") (name "unconnected-(U7-IO1-Pad1)") (class "Default")
      (node (ref "U7") (pin "1") (pinfunction "IO1_1") (pintype "passive"))
    )
    (net (code "133") (name "unconnected-(U7-IO4-Pad6)") (class "Default")
      (node (ref "U7") (pin "6") (pinfunction "IO4_6") (pintype "passive"))
    )
    (net (code "134") (name "~{VIN-FAULT}") (class "Default")
      (node (ref "MOD1") (pin "49") (pinfunction "P1_6_49") (pintype "bidirectional"))
      (node (ref "U1") (pin "10") (pinfunction "~{FAULT}_10") (pintype "output"))
    )
  )
)
